# RELAYS.net
KiCad netlist of a schematic drawn in Altium Designer
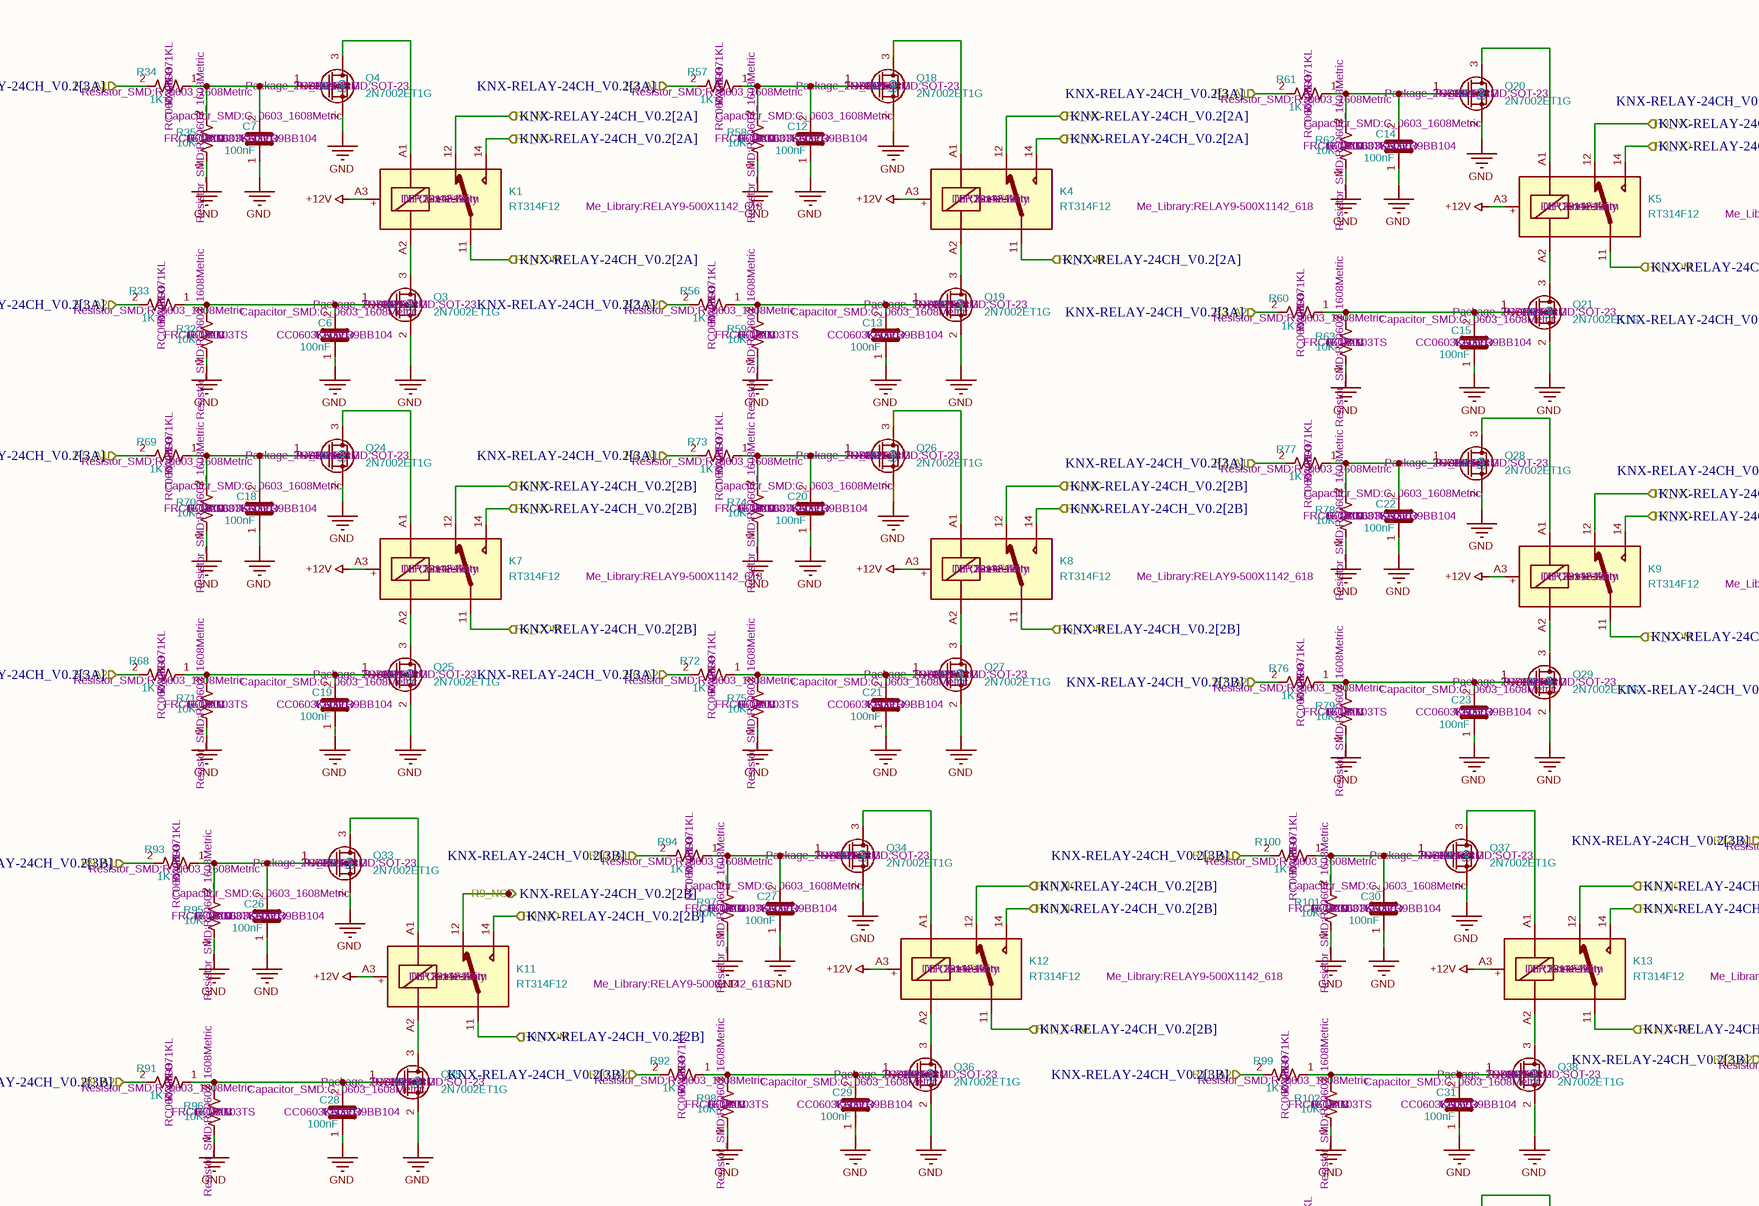
[diagram p0: RELAYS.SchDoc, top left]
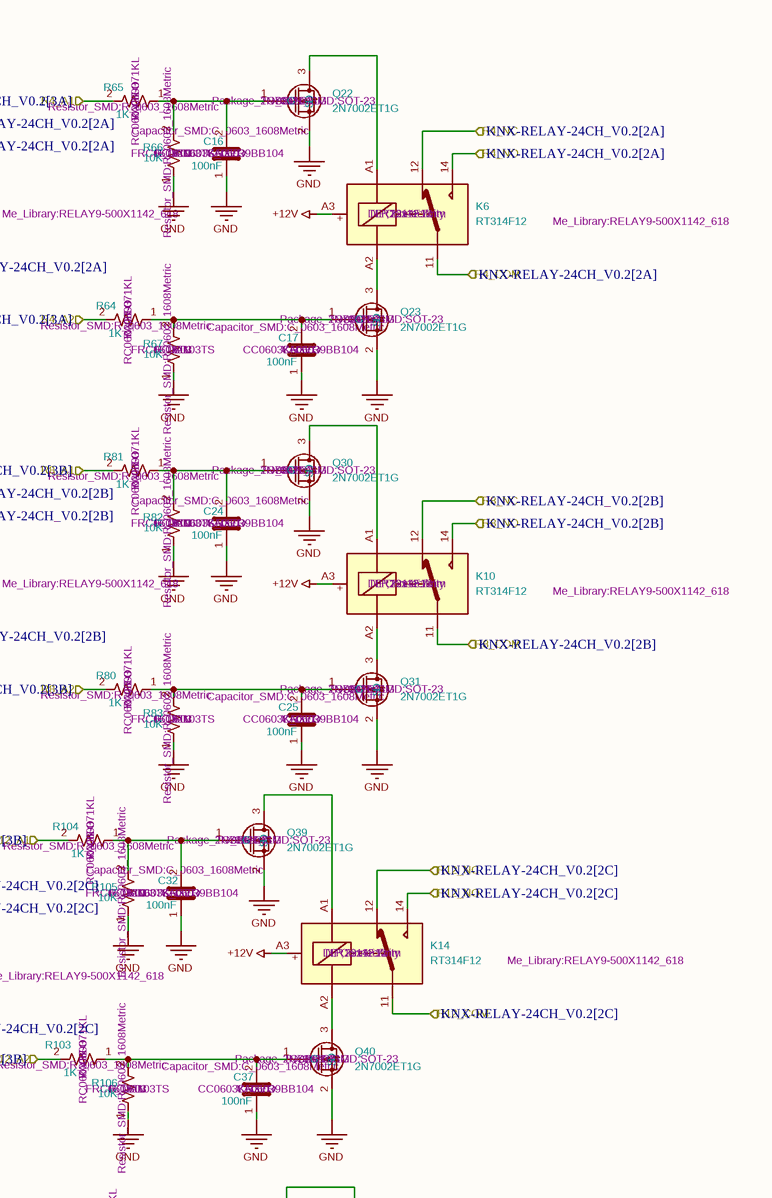
[diagram p1: RELAYS.SchDoc, top right]
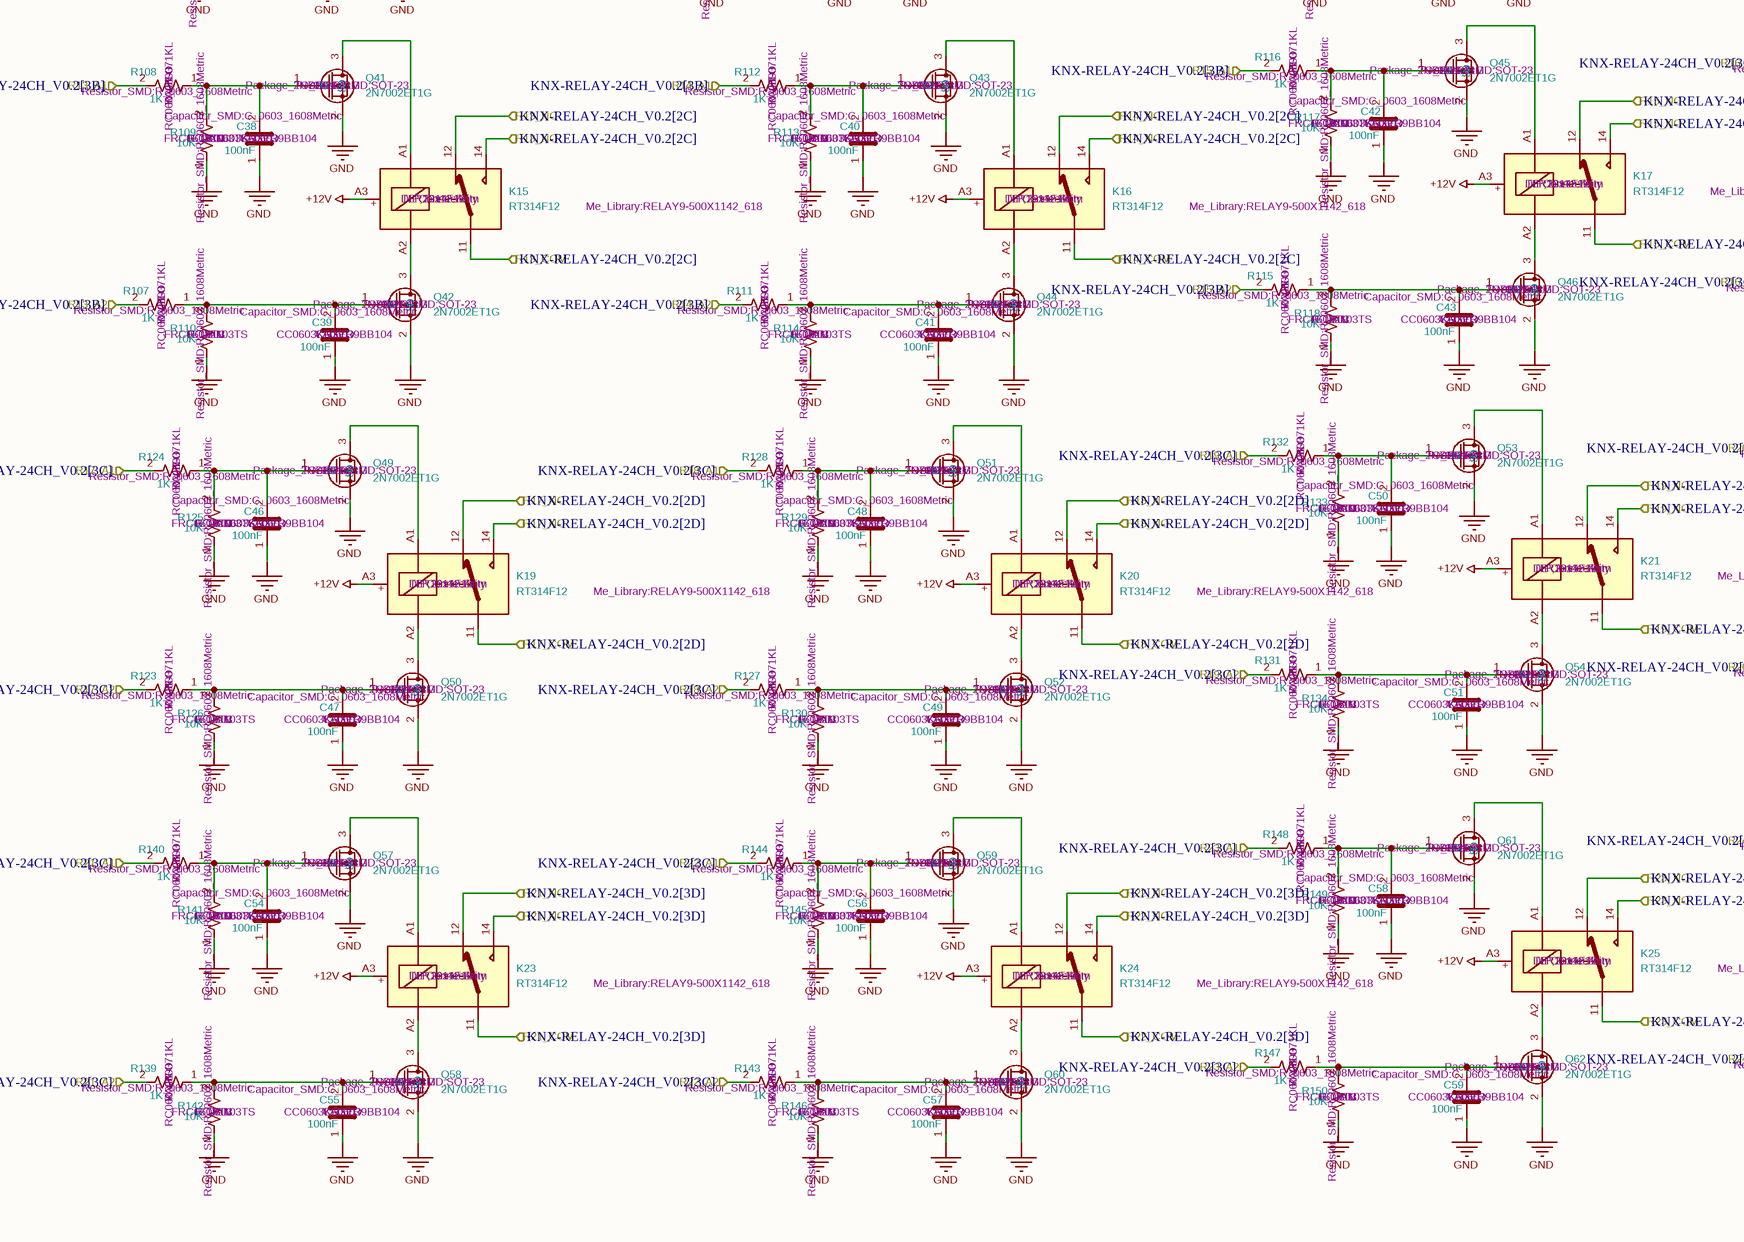
[diagram p2: RELAYS.SchDoc, bottom left]
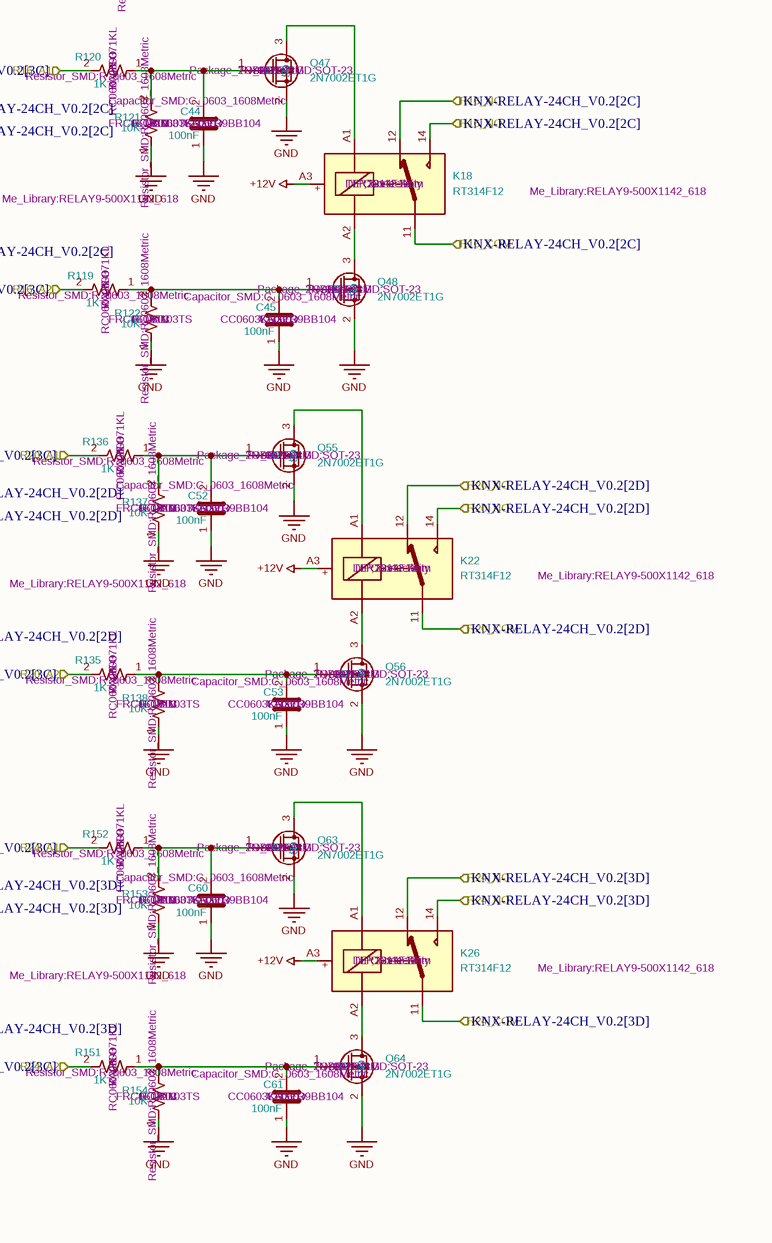
[diagram p3: RELAYS.SchDoc, bottom right]

(export (version "E")
  (design (tool "Eeschema 10.0.6"))
  (components
    (comp (ref "C6")
      (value "100nF")
      (footprint "Capacitor_SMD:C_0603_1608Metric")
      (fields
        (field (name "MANUFACTURER PART NUMBER") "CC0603KRX7R9BB104")
        (field (name "MANUFACTURER") "YAGEO")
        (field (name "PACKAGE") "C_0603")
      )
      (libsource (lib "*") (part "C_3"))
    )
    (comp (ref "C7")
      (value "100nF")
      (footprint "Capacitor_SMD:C_0603_1608Metric")
      (fields
        (field (name "MANUFACTURER PART NUMBER") "CC0603KRX7R9BB104")
        (field (name "MANUFACTURER") "YAGEO")
        (field (name "PACKAGE") "C_0603")
      )
      (libsource (lib "*") (part "C_3"))
    )
    (comp (ref "C12")
      (value "100nF")
      (footprint "Capacitor_SMD:C_0603_1608Metric")
      (fields
        (field (name "MANUFACTURER PART NUMBER") "CC0603KRX7R9BB104")
        (field (name "MANUFACTURER") "YAGEO")
        (field (name "PACKAGE") "C_0603")
      )
      (libsource (lib "*") (part "C_3"))
    )
    (comp (ref "C13")
      (value "100nF")
      (footprint "Capacitor_SMD:C_0603_1608Metric")
      (fields
        (field (name "MANUFACTURER PART NUMBER") "CC0603KRX7R9BB104")
        (field (name "MANUFACTURER") "YAGEO")
        (field (name "PACKAGE") "C_0603")
      )
      (libsource (lib "*") (part "C_3"))
    )
    (comp (ref "C14")
      (value "100nF")
      (footprint "Capacitor_SMD:C_0603_1608Metric")
      (fields
        (field (name "MANUFACTURER PART NUMBER") "CC0603KRX7R9BB104")
        (field (name "MANUFACTURER") "YAGEO")
        (field (name "PACKAGE") "C_0603")
      )
      (libsource (lib "*") (part "C_3"))
    )
    (comp (ref "C15")
      (value "100nF")
      (footprint "Capacitor_SMD:C_0603_1608Metric")
      (fields
        (field (name "MANUFACTURER PART NUMBER") "CC0603KRX7R9BB104")
        (field (name "MANUFACTURER") "YAGEO")
        (field (name "PACKAGE") "C_0603")
      )
      (libsource (lib "*") (part "C_3"))
    )
    (comp (ref "C16")
      (value "100nF")
      (footprint "Capacitor_SMD:C_0603_1608Metric")
      (fields
        (field (name "MANUFACTURER PART NUMBER") "CC0603KRX7R9BB104")
        (field (name "MANUFACTURER") "YAGEO")
        (field (name "PACKAGE") "C_0603")
      )
      (libsource (lib "*") (part "C_3"))
    )
    (comp (ref "C17")
      (value "100nF")
      (footprint "Capacitor_SMD:C_0603_1608Metric")
      (fields
        (field (name "MANUFACTURER PART NUMBER") "CC0603KRX7R9BB104")
        (field (name "MANUFACTURER") "YAGEO")
        (field (name "PACKAGE") "C_0603")
      )
      (libsource (lib "*") (part "C_3"))
    )
    (comp (ref "C18")
      (value "100nF")
      (footprint "Capacitor_SMD:C_0603_1608Metric")
      (fields
        (field (name "MANUFACTURER PART NUMBER") "CC0603KRX7R9BB104")
        (field (name "MANUFACTURER") "YAGEO")
        (field (name "PACKAGE") "C_0603")
      )
      (libsource (lib "*") (part "C_3"))
    )
    (comp (ref "C19")
      (value "100nF")
      (footprint "Capacitor_SMD:C_0603_1608Metric")
      (fields
        (field (name "MANUFACTURER PART NUMBER") "CC0603KRX7R9BB104")
        (field (name "MANUFACTURER") "YAGEO")
        (field (name "PACKAGE") "C_0603")
      )
      (libsource (lib "*") (part "C_3"))
    )
    (comp (ref "C20")
      (value "100nF")
      (footprint "Capacitor_SMD:C_0603_1608Metric")
      (fields
        (field (name "MANUFACTURER PART NUMBER") "CC0603KRX7R9BB104")
        (field (name "MANUFACTURER") "YAGEO")
        (field (name "PACKAGE") "C_0603")
      )
      (libsource (lib "*") (part "C_3"))
    )
    (comp (ref "C21")
      (value "100nF")
      (footprint "Capacitor_SMD:C_0603_1608Metric")
      (fields
        (field (name "MANUFACTURER PART NUMBER") "CC0603KRX7R9BB104")
        (field (name "MANUFACTURER") "YAGEO")
        (field (name "PACKAGE") "C_0603")
      )
      (libsource (lib "*") (part "C_3"))
    )
    (comp (ref "C22")
      (value "100nF")
      (footprint "Capacitor_SMD:C_0603_1608Metric")
      (fields
        (field (name "MANUFACTURER PART NUMBER") "CC0603KRX7R9BB104")
        (field (name "MANUFACTURER") "YAGEO")
        (field (name "PACKAGE") "C_0603")
      )
      (libsource (lib "*") (part "C_3"))
    )
    (comp (ref "C23")
      (value "100nF")
      (footprint "Capacitor_SMD:C_0603_1608Metric")
      (fields
        (field (name "MANUFACTURER PART NUMBER") "CC0603KRX7R9BB104")
        (field (name "MANUFACTURER") "YAGEO")
        (field (name "PACKAGE") "C_0603")
      )
      (libsource (lib "*") (part "C_3"))
    )
    (comp (ref "C24")
      (value "100nF")
      (footprint "Capacitor_SMD:C_0603_1608Metric")
      (fields
        (field (name "MANUFACTURER PART NUMBER") "CC0603KRX7R9BB104")
        (field (name "MANUFACTURER") "YAGEO")
        (field (name "PACKAGE") "C_0603")
      )
      (libsource (lib "*") (part "C_3"))
    )
    (comp (ref "C25")
      (value "100nF")
      (footprint "Capacitor_SMD:C_0603_1608Metric")
      (fields
        (field (name "MANUFACTURER PART NUMBER") "CC0603KRX7R9BB104")
        (field (name "MANUFACTURER") "YAGEO")
        (field (name "PACKAGE") "C_0603")
      )
      (libsource (lib "*") (part "C_3"))
    )
    (comp (ref "C26")
      (value "100nF")
      (footprint "Capacitor_SMD:C_0603_1608Metric")
      (fields
        (field (name "MANUFACTURER PART NUMBER") "CC0603KRX7R9BB104")
        (field (name "MANUFACTURER") "YAGEO")
        (field (name "PACKAGE") "C_0603")
      )
      (libsource (lib "*") (part "C_3"))
    )
    (comp (ref "C27")
      (value "100nF")
      (footprint "Capacitor_SMD:C_0603_1608Metric")
      (fields
        (field (name "MANUFACTURER PART NUMBER") "CC0603KRX7R9BB104")
        (field (name "MANUFACTURER") "YAGEO")
        (field (name "PACKAGE") "C_0603")
      )
      (libsource (lib "*") (part "C_3"))
    )
    (comp (ref "C28")
      (value "100nF")
      (footprint "Capacitor_SMD:C_0603_1608Metric")
      (fields
        (field (name "MANUFACTURER PART NUMBER") "CC0603KRX7R9BB104")
        (field (name "MANUFACTURER") "YAGEO")
        (field (name "PACKAGE") "C_0603")
      )
      (libsource (lib "*") (part "C_3"))
    )
    (comp (ref "C29")
      (value "100nF")
      (footprint "Capacitor_SMD:C_0603_1608Metric")
      (fields
        (field (name "MANUFACTURER PART NUMBER") "CC0603KRX7R9BB104")
        (field (name "MANUFACTURER") "YAGEO")
        (field (name "PACKAGE") "C_0603")
      )
      (libsource (lib "*") (part "C_3"))
    )
    (comp (ref "C30")
      (value "100nF")
      (footprint "Capacitor_SMD:C_0603_1608Metric")
      (fields
        (field (name "MANUFACTURER PART NUMBER") "CC0603KRX7R9BB104")
        (field (name "MANUFACTURER") "YAGEO")
        (field (name "PACKAGE") "C_0603")
      )
      (libsource (lib "*") (part "C_3"))
    )
    (comp (ref "C31")
      (value "100nF")
      (footprint "Capacitor_SMD:C_0603_1608Metric")
      (fields
        (field (name "MANUFACTURER PART NUMBER") "CC0603KRX7R9BB104")
        (field (name "MANUFACTURER") "YAGEO")
        (field (name "PACKAGE") "C_0603")
      )
      (libsource (lib "*") (part "C_3"))
    )
    (comp (ref "C32")
      (value "100nF")
      (footprint "Capacitor_SMD:C_0603_1608Metric")
      (fields
        (field (name "MANUFACTURER PART NUMBER") "CC0603KRX7R9BB104")
        (field (name "MANUFACTURER") "YAGEO")
        (field (name "PACKAGE") "C_0603")
      )
      (libsource (lib "*") (part "C_3"))
    )
    (comp (ref "C37")
      (value "100nF")
      (footprint "Capacitor_SMD:C_0603_1608Metric")
      (fields
        (field (name "MANUFACTURER PART NUMBER") "CC0603KRX7R9BB104")
        (field (name "MANUFACTURER") "YAGEO")
        (field (name "PACKAGE") "C_0603")
      )
      (libsource (lib "*") (part "C_3"))
    )
    (comp (ref "C38")
      (value "100nF")
      (footprint "Capacitor_SMD:C_0603_1608Metric")
      (fields
        (field (name "MANUFACTURER PART NUMBER") "CC0603KRX7R9BB104")
        (field (name "MANUFACTURER") "YAGEO")
        (field (name "PACKAGE") "C_0603")
      )
      (libsource (lib "*") (part "C_3"))
    )
    (comp (ref "C39")
      (value "100nF")
      (footprint "Capacitor_SMD:C_0603_1608Metric")
      (fields
        (field (name "MANUFACTURER PART NUMBER") "CC0603KRX7R9BB104")
        (field (name "MANUFACTURER") "YAGEO")
        (field (name "PACKAGE") "C_0603")
      )
      (libsource (lib "*") (part "C_3"))
    )
    (comp (ref "C40")
      (value "100nF")
      (footprint "Capacitor_SMD:C_0603_1608Metric")
      (fields
        (field (name "MANUFACTURER PART NUMBER") "CC0603KRX7R9BB104")
        (field (name "MANUFACTURER") "YAGEO")
        (field (name "PACKAGE") "C_0603")
      )
      (libsource (lib "*") (part "C_3"))
    )
    (comp (ref "C41")
      (value "100nF")
      (footprint "Capacitor_SMD:C_0603_1608Metric")
      (fields
        (field (name "MANUFACTURER PART NUMBER") "CC0603KRX7R9BB104")
        (field (name "MANUFACTURER") "YAGEO")
        (field (name "PACKAGE") "C_0603")
      )
      (libsource (lib "*") (part "C_3"))
    )
    (comp (ref "C42")
      (value "100nF")
      (footprint "Capacitor_SMD:C_0603_1608Metric")
      (fields
        (field (name "MANUFACTURER PART NUMBER") "CC0603KRX7R9BB104")
        (field (name "MANUFACTURER") "YAGEO")
        (field (name "PACKAGE") "C_0603")
      )
      (libsource (lib "*") (part "C_3"))
    )
    (comp (ref "C43")
      (value "100nF")
      (footprint "Capacitor_SMD:C_0603_1608Metric")
      (fields
        (field (name "MANUFACTURER PART NUMBER") "CC0603KRX7R9BB104")
        (field (name "MANUFACTURER") "YAGEO")
        (field (name "PACKAGE") "C_0603")
      )
      (libsource (lib "*") (part "C_3"))
    )
    (comp (ref "C44")
      (value "100nF")
      (footprint "Capacitor_SMD:C_0603_1608Metric")
      (fields
        (field (name "MANUFACTURER PART NUMBER") "CC0603KRX7R9BB104")
        (field (name "MANUFACTURER") "YAGEO")
        (field (name "PACKAGE") "C_0603")
      )
      (libsource (lib "*") (part "C_3"))
    )
    (comp (ref "C45")
      (value "100nF")
      (footprint "Capacitor_SMD:C_0603_1608Metric")
      (fields
        (field (name "MANUFACTURER PART NUMBER") "CC0603KRX7R9BB104")
        (field (name "MANUFACTURER") "YAGEO")
        (field (name "PACKAGE") "C_0603")
      )
      (libsource (lib "*") (part "C_3"))
    )
    (comp (ref "C46")
      (value "100nF")
      (footprint "Capacitor_SMD:C_0603_1608Metric")
      (fields
        (field (name "MANUFACTURER PART NUMBER") "CC0603KRX7R9BB104")
        (field (name "MANUFACTURER") "YAGEO")
        (field (name "PACKAGE") "C_0603")
      )
      (libsource (lib "*") (part "C_3"))
    )
    (comp (ref "C47")
      (value "100nF")
      (footprint "Capacitor_SMD:C_0603_1608Metric")
      (fields
        (field (name "MANUFACTURER PART NUMBER") "CC0603KRX7R9BB104")
        (field (name "MANUFACTURER") "YAGEO")
        (field (name "PACKAGE") "C_0603")
      )
      (libsource (lib "*") (part "C_3"))
    )
    (comp (ref "C48")
      (value "100nF")
      (footprint "Capacitor_SMD:C_0603_1608Metric")
      (fields
        (field (name "MANUFACTURER PART NUMBER") "CC0603KRX7R9BB104")
        (field (name "MANUFACTURER") "YAGEO")
        (field (name "PACKAGE") "C_0603")
      )
      (libsource (lib "*") (part "C_3"))
    )
    (comp (ref "C49")
      (value "100nF")
      (footprint "Capacitor_SMD:C_0603_1608Metric")
      (fields
        (field (name "MANUFACTURER PART NUMBER") "CC0603KRX7R9BB104")
        (field (name "MANUFACTURER") "YAGEO")
        (field (name "PACKAGE") "C_0603")
      )
      (libsource (lib "*") (part "C_3"))
    )
    (comp (ref "C50")
      (value "100nF")
      (footprint "Capacitor_SMD:C_0603_1608Metric")
      (fields
        (field (name "MANUFACTURER PART NUMBER") "CC0603KRX7R9BB104")
        (field (name "MANUFACTURER") "YAGEO")
        (field (name "PACKAGE") "C_0603")
      )
      (libsource (lib "*") (part "C_3"))
    )
    (comp (ref "C51")
      (value "100nF")
      (footprint "Capacitor_SMD:C_0603_1608Metric")
      (fields
        (field (name "MANUFACTURER PART NUMBER") "CC0603KRX7R9BB104")
        (field (name "MANUFACTURER") "YAGEO")
        (field (name "PACKAGE") "C_0603")
      )
      (libsource (lib "*") (part "C_3"))
    )
    (comp (ref "C52")
      (value "100nF")
      (footprint "Capacitor_SMD:C_0603_1608Metric")
      (fields
        (field (name "MANUFACTURER PART NUMBER") "CC0603KRX7R9BB104")
        (field (name "MANUFACTURER") "YAGEO")
        (field (name "PACKAGE") "C_0603")
      )
      (libsource (lib "*") (part "C_3"))
    )
    (comp (ref "C53")
      (value "100nF")
      (footprint "Capacitor_SMD:C_0603_1608Metric")
      (fields
        (field (name "MANUFACTURER PART NUMBER") "CC0603KRX7R9BB104")
        (field (name "MANUFACTURER") "YAGEO")
        (field (name "PACKAGE") "C_0603")
      )
      (libsource (lib "*") (part "C_3"))
    )
    (comp (ref "C54")
      (value "100nF")
      (footprint "Capacitor_SMD:C_0603_1608Metric")
      (fields
        (field (name "MANUFACTURER PART NUMBER") "CC0603KRX7R9BB104")
        (field (name "MANUFACTURER") "YAGEO")
        (field (name "PACKAGE") "C_0603")
      )
      (libsource (lib "*") (part "C_3"))
    )
    (comp (ref "C55")
      (value "100nF")
      (footprint "Capacitor_SMD:C_0603_1608Metric")
      (fields
        (field (name "MANUFACTURER PART NUMBER") "CC0603KRX7R9BB104")
        (field (name "MANUFACTURER") "YAGEO")
        (field (name "PACKAGE") "C_0603")
      )
      (libsource (lib "*") (part "C_3"))
    )
    (comp (ref "C56")
      (value "100nF")
      (footprint "Capacitor_SMD:C_0603_1608Metric")
      (fields
        (field (name "MANUFACTURER PART NUMBER") "CC0603KRX7R9BB104")
        (field (name "MANUFACTURER") "YAGEO")
        (field (name "PACKAGE") "C_0603")
      )
      (libsource (lib "*") (part "C_3"))
    )
    (comp (ref "C57")
      (value "100nF")
      (footprint "Capacitor_SMD:C_0603_1608Metric")
      (fields
        (field (name "MANUFACTURER PART NUMBER") "CC0603KRX7R9BB104")
        (field (name "MANUFACTURER") "YAGEO")
        (field (name "PACKAGE") "C_0603")
      )
      (libsource (lib "*") (part "C_3"))
    )
    (comp (ref "C58")
      (value "100nF")
      (footprint "Capacitor_SMD:C_0603_1608Metric")
      (fields
        (field (name "MANUFACTURER PART NUMBER") "CC0603KRX7R9BB104")
        (field (name "MANUFACTURER") "YAGEO")
        (field (name "PACKAGE") "C_0603")
      )
      (libsource (lib "*") (part "C_3"))
    )
    (comp (ref "C59")
      (value "100nF")
      (footprint "Capacitor_SMD:C_0603_1608Metric")
      (fields
        (field (name "MANUFACTURER PART NUMBER") "CC0603KRX7R9BB104")
        (field (name "MANUFACTURER") "YAGEO")
        (field (name "PACKAGE") "C_0603")
      )
      (libsource (lib "*") (part "C_3"))
    )
    (comp (ref "C60")
      (value "100nF")
      (footprint "Capacitor_SMD:C_0603_1608Metric")
      (fields
        (field (name "MANUFACTURER PART NUMBER") "CC0603KRX7R9BB104")
        (field (name "MANUFACTURER") "YAGEO")
        (field (name "PACKAGE") "C_0603")
      )
      (libsource (lib "*") (part "C_3"))
    )
    (comp (ref "C61")
      (value "100nF")
      (footprint "Capacitor_SMD:C_0603_1608Metric")
      (fields
        (field (name "MANUFACTURER PART NUMBER") "CC0603KRX7R9BB104")
        (field (name "MANUFACTURER") "YAGEO")
        (field (name "PACKAGE") "C_0603")
      )
      (libsource (lib "*") (part "C_3"))
    )
    (comp (ref "K1")
      (value "RT314F12")
      (footprint "Me_Library:RELAY9-500X1142_618")
      (fields
        (field (name "MANUFACTURER PART NUMBER") "RT314F12")
        (field (name "MANUFACTURER") "TE Connectivity")
        (field (name "PACKAGE") "DIP,29x12.7mm")
      )
      (libsource (lib "Me_Library") (part "RT314A03"))
    )
    (comp (ref "K4")
      (value "RT314F12")
      (footprint "Me_Library:RELAY9-500X1142_618")
      (fields
        (field (name "MANUFACTURER PART NUMBER") "RT314F12")
        (field (name "MANUFACTURER") "TE Connectivity")
        (field (name "PACKAGE") "DIP,29x12.7mm")
      )
      (libsource (lib "Me_Library") (part "RT314A03"))
    )
    (comp (ref "K5")
      (value "RT314F12")
      (footprint "Me_Library:RELAY9-500X1142_618")
      (fields
        (field (name "MANUFACTURER PART NUMBER") "RT314F12")
        (field (name "MANUFACTURER") "TE Connectivity")
        (field (name "PACKAGE") "DIP,29x12.7mm")
      )
      (libsource (lib "Me_Library") (part "RT314A03"))
    )
    (comp (ref "K6")
      (value "RT314F12")
      (footprint "Me_Library:RELAY9-500X1142_618")
      (fields
        (field (name "MANUFACTURER PART NUMBER") "RT314F12")
        (field (name "MANUFACTURER") "TE Connectivity")
        (field (name "PACKAGE") "DIP,29x12.7mm")
      )
      (libsource (lib "Me_Library") (part "RT314A03"))
    )
    (comp (ref "K7")
      (value "RT314F12")
      (footprint "Me_Library:RELAY9-500X1142_618")
      (fields
        (field (name "MANUFACTURER PART NUMBER") "RT314F12")
        (field (name "MANUFACTURER") "TE Connectivity")
        (field (name "PACKAGE") "DIP,29x12.7mm")
      )
      (libsource (lib "Me_Library") (part "RT314A03"))
    )
    (comp (ref "K8")
      (value "RT314F12")
      (footprint "Me_Library:RELAY9-500X1142_618")
      (fields
        (field (name "MANUFACTURER PART NUMBER") "RT314F12")
        (field (name "MANUFACTURER") "TE Connectivity")
        (field (name "PACKAGE") "DIP,29x12.7mm")
      )
      (libsource (lib "Me_Library") (part "RT314A03"))
    )
    (comp (ref "K9")
      (value "RT314F12")
      (footprint "Me_Library:RELAY9-500X1142_618")
      (fields
        (field (name "MANUFACTURER PART NUMBER") "RT314F12")
        (field (name "MANUFACTURER") "TE Connectivity")
        (field (name "PACKAGE") "DIP,29x12.7mm")
      )
      (libsource (lib "Me_Library") (part "RT314A03"))
    )
    (comp (ref "K10")
      (value "RT314F12")
      (footprint "Me_Library:RELAY9-500X1142_618")
      (fields
        (field (name "MANUFACTURER PART NUMBER") "RT314F12")
        (field (name "MANUFACTURER") "TE Connectivity")
        (field (name "PACKAGE") "DIP,29x12.7mm")
      )
      (libsource (lib "Me_Library") (part "RT314A03"))
    )
    (comp (ref "K11")
      (value "RT314F12")
      (footprint "Me_Library:RELAY9-500X1142_618")
      (fields
        (field (name "MANUFACTURER PART NUMBER") "RT314F12")
        (field (name "MANUFACTURER") "TE Connectivity")
        (field (name "PACKAGE") "DIP,29x12.7mm")
      )
      (libsource (lib "Me_Library") (part "RT314A03"))
    )
    (comp (ref "K12")
      (value "RT314F12")
      (footprint "Me_Library:RELAY9-500X1142_618")
      (fields
        (field (name "MANUFACTURER PART NUMBER") "RT314F12")
        (field (name "MANUFACTURER") "TE Connectivity")
        (field (name "PACKAGE") "DIP,29x12.7mm")
      )
      (libsource (lib "Me_Library") (part "RT314A03"))
    )
    (comp (ref "K13")
      (value "RT314F12")
      (footprint "Me_Library:RELAY9-500X1142_618")
      (fields
        (field (name "MANUFACTURER PART NUMBER") "RT314F12")
        (field (name "MANUFACTURER") "TE Connectivity")
        (field (name "PACKAGE") "DIP,29x12.7mm")
      )
      (libsource (lib "Me_Library") (part "RT314A03"))
    )
    (comp (ref "K14")
      (value "RT314F12")
      (footprint "Me_Library:RELAY9-500X1142_618")
      (fields
        (field (name "MANUFACTURER PART NUMBER") "RT314F12")
        (field (name "MANUFACTURER") "TE Connectivity")
        (field (name "PACKAGE") "DIP,29x12.7mm")
      )
      (libsource (lib "Me_Library") (part "RT314A03"))
    )
    (comp (ref "K15")
      (value "RT314F12")
      (footprint "Me_Library:RELAY9-500X1142_618")
      (fields
        (field (name "MANUFACTURER PART NUMBER") "RT314F12")
        (field (name "MANUFACTURER") "TE Connectivity")
        (field (name "PACKAGE") "DIP,29x12.7mm")
      )
      (libsource (lib "Me_Library") (part "RT314A03"))
    )
    (comp (ref "K16")
      (value "RT314F12")
      (footprint "Me_Library:RELAY9-500X1142_618")
      (fields
        (field (name "MANUFACTURER PART NUMBER") "RT314F12")
        (field (name "MANUFACTURER") "TE Connectivity")
        (field (name "PACKAGE") "DIP,29x12.7mm")
      )
      (libsource (lib "Me_Library") (part "RT314A03"))
    )
    (comp (ref "K17")
      (value "RT314F12")
      (footprint "Me_Library:RELAY9-500X1142_618")
      (fields
        (field (name "MANUFACTURER PART NUMBER") "RT314F12")
        (field (name "MANUFACTURER") "TE Connectivity")
        (field (name "PACKAGE") "DIP,29x12.7mm")
      )
      (libsource (lib "Me_Library") (part "RT314A03"))
    )
    (comp (ref "K18")
      (value "RT314F12")
      (footprint "Me_Library:RELAY9-500X1142_618")
      (fields
        (field (name "MANUFACTURER PART NUMBER") "RT314F12")
        (field (name "MANUFACTURER") "TE Connectivity")
        (field (name "PACKAGE") "DIP,29x12.7mm")
      )
      (libsource (lib "Me_Library") (part "RT314A03"))
    )
    (comp (ref "K19")
      (value "RT314F12")
      (footprint "Me_Library:RELAY9-500X1142_618")
      (fields
        (field (name "MANUFACTURER PART NUMBER") "RT314F12")
        (field (name "MANUFACTURER") "TE Connectivity")
        (field (name "PACKAGE") "DIP,29x12.7mm")
      )
      (libsource (lib "Me_Library") (part "RT314A03"))
    )
    (comp (ref "K20")
      (value "RT314F12")
      (footprint "Me_Library:RELAY9-500X1142_618")
      (fields
        (field (name "MANUFACTURER PART NUMBER") "RT314F12")
        (field (name "MANUFACTURER") "TE Connectivity")
        (field (name "PACKAGE") "DIP,29x12.7mm")
      )
      (libsource (lib "Me_Library") (part "RT314A03"))
    )
    (comp (ref "K21")
      (value "RT314F12")
      (footprint "Me_Library:RELAY9-500X1142_618")
      (fields
        (field (name "MANUFACTURER PART NUMBER") "RT314F12")
        (field (name "MANUFACTURER") "TE Connectivity")
        (field (name "PACKAGE") "DIP,29x12.7mm")
      )
      (libsource (lib "Me_Library") (part "RT314A03"))
    )
    (comp (ref "K22")
      (value "RT314F12")
      (footprint "Me_Library:RELAY9-500X1142_618")
      (fields
        (field (name "MANUFACTURER PART NUMBER") "RT314F12")
        (field (name "MANUFACTURER") "TE Connectivity")
        (field (name "PACKAGE") "DIP,29x12.7mm")
      )
      (libsource (lib "Me_Library") (part "RT314A03"))
    )
    (comp (ref "K23")
      (value "RT314F12")
      (footprint "Me_Library:RELAY9-500X1142_618")
      (fields
        (field (name "MANUFACTURER PART NUMBER") "RT314F12")
        (field (name "MANUFACTURER") "TE Connectivity")
        (field (name "PACKAGE") "DIP,29x12.7mm")
      )
      (libsource (lib "Me_Library") (part "RT314A03"))
    )
    (comp (ref "K24")
      (value "RT314F12")
      (footprint "Me_Library:RELAY9-500X1142_618")
      (fields
        (field (name "MANUFACTURER PART NUMBER") "RT314F12")
        (field (name "MANUFACTURER") "TE Connectivity")
        (field (name "PACKAGE") "DIP,29x12.7mm")
      )
      (libsource (lib "Me_Library") (part "RT314A03"))
    )
    (comp (ref "K25")
      (value "RT314F12")
      (footprint "Me_Library:RELAY9-500X1142_618")
      (fields
        (field (name "MANUFACTURER PART NUMBER") "RT314F12")
        (field (name "MANUFACTURER") "TE Connectivity")
        (field (name "PACKAGE") "DIP,29x12.7mm")
      )
      (libsource (lib "Me_Library") (part "RT314A03"))
    )
    (comp (ref "K26")
      (value "RT314F12")
      (footprint "Me_Library:RELAY9-500X1142_618")
      (fields
        (field (name "MANUFACTURER PART NUMBER") "RT314F12")
        (field (name "MANUFACTURER") "TE Connectivity")
        (field (name "PACKAGE") "DIP,29x12.7mm")
      )
      (libsource (lib "Me_Library") (part "RT314A03"))
    )
    (comp (ref "Q3")
      (value "2N7002ET1G")
      (footprint "Package_TO_SOT_SMD:SOT-23")
      (fields
        (field (name "MANUFACTURER PART NUMBER") "2N7002ET1G")
        (field (name "MANUFACTURER") "onsemi")
        (field (name "PACKAGE") "SOT-23")
      )
      (libsource (lib "Transistor_FET_Other") (part "Q_NMOS_Depletion_GSD"))
    )
    (comp (ref "Q4")
      (value "2N7002ET1G")
      (footprint "Package_TO_SOT_SMD:SOT-23")
      (fields
        (field (name "MANUFACTURER PART NUMBER") "2N7002ET1G")
        (field (name "MANUFACTURER") "onsemi")
        (field (name "PACKAGE") "SOT-23")
      )
      (libsource (lib "Transistor_FET_Other") (part "Q_NMOS_Depletion_GSD"))
    )
    (comp (ref "Q18")
      (value "2N7002ET1G")
      (footprint "Package_TO_SOT_SMD:SOT-23")
      (fields
        (field (name "MANUFACTURER PART NUMBER") "2N7002ET1G")
        (field (name "MANUFACTURER") "onsemi")
        (field (name "PACKAGE") "SOT-23")
      )
      (libsource (lib "Transistor_FET_Other") (part "Q_NMOS_Depletion_GSD"))
    )
    (comp (ref "Q19")
      (value "2N7002ET1G")
      (footprint "Package_TO_SOT_SMD:SOT-23")
      (fields
        (field (name "MANUFACTURER PART NUMBER") "2N7002ET1G")
        (field (name "MANUFACTURER") "onsemi")
        (field (name "PACKAGE") "SOT-23")
      )
      (libsource (lib "Transistor_FET_Other") (part "Q_NMOS_Depletion_GSD"))
    )
    (comp (ref "Q20")
      (value "2N7002ET1G")
      (footprint "Package_TO_SOT_SMD:SOT-23")
      (fields
        (field (name "MANUFACTURER PART NUMBER") "2N7002ET1G")
        (field (name "MANUFACTURER") "onsemi")
        (field (name "PACKAGE") "SOT-23")
      )
      (libsource (lib "Transistor_FET_Other") (part "Q_NMOS_Depletion_GSD"))
    )
    (comp (ref "Q21")
      (value "2N7002ET1G")
      (footprint "Package_TO_SOT_SMD:SOT-23")
      (fields
        (field (name "MANUFACTURER PART NUMBER") "2N7002ET1G")
        (field (name "MANUFACTURER") "onsemi")
        (field (name "PACKAGE") "SOT-23")
      )
      (libsource (lib "Transistor_FET_Other") (part "Q_NMOS_Depletion_GSD"))
    )
    (comp (ref "Q22")
      (value "2N7002ET1G")
      (footprint "Package_TO_SOT_SMD:SOT-23")
      (fields
        (field (name "MANUFACTURER PART NUMBER") "2N7002ET1G")
        (field (name "MANUFACTURER") "onsemi")
        (field (name "PACKAGE") "SOT-23")
      )
      (libsource (lib "Transistor_FET_Other") (part "Q_NMOS_Depletion_GSD"))
    )
    (comp (ref "Q23")
      (value "2N7002ET1G")
      (footprint "Package_TO_SOT_SMD:SOT-23")
      (fields
        (field (name "MANUFACTURER PART NUMBER") "2N7002ET1G")
        (field (name "MANUFACTURER") "onsemi")
        (field (name "PACKAGE") "SOT-23")
      )
      (libsource (lib "Transistor_FET_Other") (part "Q_NMOS_Depletion_GSD"))
    )
    (comp (ref "Q24")
      (value "2N7002ET1G")
      (footprint "Package_TO_SOT_SMD:SOT-23")
      (fields
        (field (name "MANUFACTURER PART NUMBER") "2N7002ET1G")
        (field (name "MANUFACTURER") "onsemi")
        (field (name "PACKAGE") "SOT-23")
      )
      (libsource (lib "Transistor_FET_Other") (part "Q_NMOS_Depletion_GSD"))
    )
    (comp (ref "Q25")
      (value "2N7002ET1G")
      (footprint "Package_TO_SOT_SMD:SOT-23")
      (fields
        (field (name "MANUFACTURER PART NUMBER") "2N7002ET1G")
        (field (name "MANUFACTURER") "onsemi")
        (field (name "PACKAGE") "SOT-23")
      )
      (libsource (lib "Transistor_FET_Other") (part "Q_NMOS_Depletion_GSD"))
    )
    (comp (ref "Q26")
      (value "2N7002ET1G")
      (footprint "Package_TO_SOT_SMD:SOT-23")
      (fields
        (field (name "MANUFACTURER PART NUMBER") "2N7002ET1G")
        (field (name "MANUFACTURER") "onsemi")
        (field (name "PACKAGE") "SOT-23")
      )
      (libsource (lib "Transistor_FET_Other") (part "Q_NMOS_Depletion_GSD"))
    )
    (comp (ref "Q27")
      (value "2N7002ET1G")
      (footprint "Package_TO_SOT_SMD:SOT-23")
      (fields
        (field (name "MANUFACTURER PART NUMBER") "2N7002ET1G")
        (field (name "MANUFACTURER") "onsemi")
        (field (name "PACKAGE") "SOT-23")
      )
      (libsource (lib "Transistor_FET_Other") (part "Q_NMOS_Depletion_GSD"))
    )
    (comp (ref "Q28")
      (value "2N7002ET1G")
      (footprint "Package_TO_SOT_SMD:SOT-23")
      (fields
        (field (name "MANUFACTURER PART NUMBER") "2N7002ET1G")
        (field (name "MANUFACTURER") "onsemi")
        (field (name "PACKAGE") "SOT-23")
      )
      (libsource (lib "Transistor_FET_Other") (part "Q_NMOS_Depletion_GSD"))
    )
    (comp (ref "Q29")
      (value "2N7002ET1G")
      (footprint "Package_TO_SOT_SMD:SOT-23")
      (fields
        (field (name "MANUFACTURER PART NUMBER") "2N7002ET1G")
        (field (name "MANUFACTURER") "onsemi")
        (field (name "PACKAGE") "SOT-23")
      )
      (libsource (lib "Transistor_FET_Other") (part "Q_NMOS_Depletion_GSD"))
    )
    (comp (ref "Q30")
      (value "2N7002ET1G")
      (footprint "Package_TO_SOT_SMD:SOT-23")
      (fields
        (field (name "MANUFACTURER PART NUMBER") "2N7002ET1G")
        (field (name "MANUFACTURER") "onsemi")
        (field (name "PACKAGE") "SOT-23")
      )
      (libsource (lib "Transistor_FET_Other") (part "Q_NMOS_Depletion_GSD"))
    )
    (comp (ref "Q31")
      (value "2N7002ET1G")
      (footprint "Package_TO_SOT_SMD:SOT-23")
      (fields
        (field (name "MANUFACTURER PART NUMBER") "2N7002ET1G")
        (field (name "MANUFACTURER") "onsemi")
        (field (name "PACKAGE") "SOT-23")
      )
      (libsource (lib "Transistor_FET_Other") (part "Q_NMOS_Depletion_GSD"))
    )
    (comp (ref "Q33")
      (value "2N7002ET1G")
      (footprint "Package_TO_SOT_SMD:SOT-23")
      (fields
        (field (name "MANUFACTURER PART NUMBER") "2N7002ET1G")
        (field (name "MANUFACTURER") "onsemi")
        (field (name "PACKAGE") "SOT-23")
      )
      (libsource (lib "Transistor_FET_Other") (part "Q_NMOS_Depletion_GSD"))
    )
    (comp (ref "Q34")
      (value "2N7002ET1G")
      (footprint "Package_TO_SOT_SMD:SOT-23")
      (fields
        (field (name "MANUFACTURER PART NUMBER") "2N7002ET1G")
        (field (name "MANUFACTURER") "onsemi")
        (field (name "PACKAGE") "SOT-23")
      )
      (libsource (lib "Transistor_FET_Other") (part "Q_NMOS_Depletion_GSD"))
    )
    (comp (ref "Q35")
      (value "2N7002ET1G")
      (footprint "Package_TO_SOT_SMD:SOT-23")
      (fields
        (field (name "MANUFACTURER PART NUMBER") "2N7002ET1G")
        (field (name "MANUFACTURER") "onsemi")
        (field (name "PACKAGE") "SOT-23")
      )
      (libsource (lib "Transistor_FET_Other") (part "Q_NMOS_Depletion_GSD"))
    )
    (comp (ref "Q36")
      (value "2N7002ET1G")
      (footprint "Package_TO_SOT_SMD:SOT-23")
      (fields
        (field (name "MANUFACTURER PART NUMBER") "2N7002ET1G")
        (field (name "MANUFACTURER") "onsemi")
        (field (name "PACKAGE") "SOT-23")
      )
      (libsource (lib "Transistor_FET_Other") (part "Q_NMOS_Depletion_GSD"))
    )
    (comp (ref "Q37")
      (value "2N7002ET1G")
      (footprint "Package_TO_SOT_SMD:SOT-23")
      (fields
        (field (name "MANUFACTURER PART NUMBER") "2N7002ET1G")
        (field (name "MANUFACTURER") "onsemi")
        (field (name "PACKAGE") "SOT-23")
      )
      (libsource (lib "Transistor_FET_Other") (part "Q_NMOS_Depletion_GSD"))
    )
    (comp (ref "Q38")
      (value "2N7002ET1G")
      (footprint "Package_TO_SOT_SMD:SOT-23")
      (fields
        (field (name "MANUFACTURER PART NUMBER") "2N7002ET1G")
        (field (name "MANUFACTURER") "onsemi")
        (field (name "PACKAGE") "SOT-23")
      )
      (libsource (lib "Transistor_FET_Other") (part "Q_NMOS_Depletion_GSD"))
    )
    (comp (ref "Q39")
      (value "2N7002ET1G")
      (footprint "Package_TO_SOT_SMD:SOT-23")
      (fields
        (field (name "MANUFACTURER PART NUMBER") "2N7002ET1G")
        (field (name "MANUFACTURER") "onsemi")
        (field (name "PACKAGE") "SOT-23")
      )
      (libsource (lib "Transistor_FET_Other") (part "Q_NMOS_Depletion_GSD"))
    )
    (comp (ref "Q40")
      (value "2N7002ET1G")
      (footprint "Package_TO_SOT_SMD:SOT-23")
      (fields
        (field (name "MANUFACTURER PART NUMBER") "2N7002ET1G")
        (field (name "MANUFACTURER") "onsemi")
        (field (name "PACKAGE") "SOT-23")
      )
      (libsource (lib "Transistor_FET_Other") (part "Q_NMOS_Depletion_GSD"))
    )
    (comp (ref "Q41")
      (value "2N7002ET1G")
      (footprint "Package_TO_SOT_SMD:SOT-23")
      (fields
        (field (name "MANUFACTURER PART NUMBER") "2N7002ET1G")
        (field (name "MANUFACTURER") "onsemi")
        (field (name "PACKAGE") "SOT-23")
      )
      (libsource (lib "Transistor_FET_Other") (part "Q_NMOS_Depletion_GSD"))
    )
    (comp (ref "Q42")
      (value "2N7002ET1G")
      (footprint "Package_TO_SOT_SMD:SOT-23")
      (fields
        (field (name "MANUFACTURER PART NUMBER") "2N7002ET1G")
        (field (name "MANUFACTURER") "onsemi")
        (field (name "PACKAGE") "SOT-23")
      )
      (libsource (lib "Transistor_FET_Other") (part "Q_NMOS_Depletion_GSD"))
    )
    (comp (ref "Q43")
      (value "2N7002ET1G")
      (footprint "Package_TO_SOT_SMD:SOT-23")
      (fields
        (field (name "MANUFACTURER PART NUMBER") "2N7002ET1G")
        (field (name "MANUFACTURER") "onsemi")
        (field (name "PACKAGE") "SOT-23")
      )
      (libsource (lib "Transistor_FET_Other") (part "Q_NMOS_Depletion_GSD"))
    )
    (comp (ref "Q44")
      (value "2N7002ET1G")
      (footprint "Package_TO_SOT_SMD:SOT-23")
      (fields
        (field (name "MANUFACTURER PART NUMBER") "2N7002ET1G")
        (field (name "MANUFACTURER") "onsemi")
        (field (name "PACKAGE") "SOT-23")
      )
      (libsource (lib "Transistor_FET_Other") (part "Q_NMOS_Depletion_GSD"))
    )
    (comp (ref "Q45")
      (value "2N7002ET1G")
      (footprint "Package_TO_SOT_SMD:SOT-23")
      (fields
        (field (name "MANUFACTURER PART NUMBER") "2N7002ET1G")
        (field (name "MANUFACTURER") "onsemi")
        (field (name "PACKAGE") "SOT-23")
      )
      (libsource (lib "Transistor_FET_Other") (part "Q_NMOS_Depletion_GSD"))
    )
    (comp (ref "Q46")
      (value "2N7002ET1G")
      (footprint "Package_TO_SOT_SMD:SOT-23")
      (fields
        (field (name "MANUFACTURER PART NUMBER") "2N7002ET1G")
        (field (name "MANUFACTURER") "onsemi")
        (field (name "PACKAGE") "SOT-23")
      )
      (libsource (lib "Transistor_FET_Other") (part "Q_NMOS_Depletion_GSD"))
    )
    (comp (ref "Q47")
      (value "2N7002ET1G")
      (footprint "Package_TO_SOT_SMD:SOT-23")
      (fields
        (field (name "MANUFACTURER PART NUMBER") "2N7002ET1G")
        (field (name "MANUFACTURER") "onsemi")
        (field (name "PACKAGE") "SOT-23")
      )
      (libsource (lib "Transistor_FET_Other") (part "Q_NMOS_Depletion_GSD"))
    )
    (comp (ref "Q48")
      (value "2N7002ET1G")
      (footprint "Package_TO_SOT_SMD:SOT-23")
      (fields
        (field (name "MANUFACTURER PART NUMBER") "2N7002ET1G")
        (field (name "MANUFACTURER") "onsemi")
        (field (name "PACKAGE") "SOT-23")
      )
      (libsource (lib "Transistor_FET_Other") (part "Q_NMOS_Depletion_GSD"))
    )
    (comp (ref "Q49")
      (value "2N7002ET1G")
      (footprint "Package_TO_SOT_SMD:SOT-23")
      (fields
        (field (name "MANUFACTURER PART NUMBER") "2N7002ET1G")
        (field (name "MANUFACTURER") "onsemi")
        (field (name "PACKAGE") "SOT-23")
      )
      (libsource (lib "Transistor_FET_Other") (part "Q_NMOS_Depletion_GSD"))
    )
    (comp (ref "Q50")
      (value "2N7002ET1G")
      (footprint "Package_TO_SOT_SMD:SOT-23")
      (fields
        (field (name "MANUFACTURER PART NUMBER") "2N7002ET1G")
        (field (name "MANUFACTURER") "onsemi")
        (field (name "PACKAGE") "SOT-23")
      )
      (libsource (lib "Transistor_FET_Other") (part "Q_NMOS_Depletion_GSD"))
    )
    (comp (ref "Q51")
      (value "2N7002ET1G")
      (footprint "Package_TO_SOT_SMD:SOT-23")
      (fields
        (field (name "MANUFACTURER PART NUMBER") "2N7002ET1G")
        (field (name "MANUFACTURER") "onsemi")
        (field (name "PACKAGE") "SOT-23")
      )
      (libsource (lib "Transistor_FET_Other") (part "Q_NMOS_Depletion_GSD"))
    )
    (comp (ref "Q52")
      (value "2N7002ET1G")
      (footprint "Package_TO_SOT_SMD:SOT-23")
      (fields
        (field (name "MANUFACTURER PART NUMBER") "2N7002ET1G")
        (field (name "MANUFACTURER") "onsemi")
        (field (name "PACKAGE") "SOT-23")
      )
      (libsource (lib "Transistor_FET_Other") (part "Q_NMOS_Depletion_GSD"))
    )
    (comp (ref "Q53")
      (value "2N7002ET1G")
      (footprint "Package_TO_SOT_SMD:SOT-23")
      (fields
        (field (name "MANUFACTURER PART NUMBER") "2N7002ET1G")
        (field (name "MANUFACTURER") "onsemi")
        (field (name "PACKAGE") "SOT-23")
      )
      (libsource (lib "Transistor_FET_Other") (part "Q_NMOS_Depletion_GSD"))
    )
    (comp (ref "Q54")
      (value "2N7002ET1G")
      (footprint "Package_TO_SOT_SMD:SOT-23")
      (fields
        (field (name "MANUFACTURER PART NUMBER") "2N7002ET1G")
        (field (name "MANUFACTURER") "onsemi")
        (field (name "PACKAGE") "SOT-23")
      )
      (libsource (lib "Transistor_FET_Other") (part "Q_NMOS_Depletion_GSD"))
    )
    (comp (ref "Q55")
      (value "2N7002ET1G")
      (footprint "Package_TO_SOT_SMD:SOT-23")
      (fields
        (field (name "MANUFACTURER PART NUMBER") "2N7002ET1G")
        (field (name "MANUFACTURER") "onsemi")
        (field (name "PACKAGE") "SOT-23")
      )
      (libsource (lib "Transistor_FET_Other") (part "Q_NMOS_Depletion_GSD"))
    )
    (comp (ref "Q56")
      (value "2N7002ET1G")
      (footprint "Package_TO_SOT_SMD:SOT-23")
      (fields
        (field (name "MANUFACTURER PART NUMBER") "2N7002ET1G")
        (field (name "MANUFACTURER") "onsemi")
        (field (name "PACKAGE") "SOT-23")
      )
      (libsource (lib "Transistor_FET_Other") (part "Q_NMOS_Depletion_GSD"))
    )
    (comp (ref "Q57")
      (value "2N7002ET1G")
      (footprint "Package_TO_SOT_SMD:SOT-23")
      (fields
        (field (name "MANUFACTURER PART NUMBER") "2N7002ET1G")
        (field (name "MANUFACTURER") "onsemi")
        (field (name "PACKAGE") "SOT-23")
      )
      (libsource (lib "Transistor_FET_Other") (part "Q_NMOS_Depletion_GSD"))
    )
    (comp (ref "Q58")
      (value "2N7002ET1G")
      (footprint "Package_TO_SOT_SMD:SOT-23")
      (fields
        (field (name "MANUFACTURER PART NUMBER") "2N7002ET1G")
        (field (name "MANUFACTURER") "onsemi")
        (field (name "PACKAGE") "SOT-23")
      )
      (libsource (lib "Transistor_FET_Other") (part "Q_NMOS_Depletion_GSD"))
    )
    (comp (ref "Q59")
      (value "2N7002ET1G")
      (footprint "Package_TO_SOT_SMD:SOT-23")
      (fields
        (field (name "MANUFACTURER PART NUMBER") "2N7002ET1G")
        (field (name "MANUFACTURER") "onsemi")
        (field (name "PACKAGE") "SOT-23")
      )
      (libsource (lib "Transistor_FET_Other") (part "Q_NMOS_Depletion_GSD"))
    )
    (comp (ref "Q60")
      (value "2N7002ET1G")
      (footprint "Package_TO_SOT_SMD:SOT-23")
      (fields
        (field (name "MANUFACTURER PART NUMBER") "2N7002ET1G")
        (field (name "MANUFACTURER") "onsemi")
        (field (name "PACKAGE") "SOT-23")
      )
      (libsource (lib "Transistor_FET_Other") (part "Q_NMOS_Depletion_GSD"))
    )
    (comp (ref "Q61")
      (value "2N7002ET1G")
      (footprint "Package_TO_SOT_SMD:SOT-23")
      (fields
        (field (name "MANUFACTURER PART NUMBER") "2N7002ET1G")
        (field (name "MANUFACTURER") "onsemi")
        (field (name "PACKAGE") "SOT-23")
      )
      (libsource (lib "Transistor_FET_Other") (part "Q_NMOS_Depletion_GSD"))
    )
    (comp (ref "Q62")
      (value "2N7002ET1G")
      (footprint "Package_TO_SOT_SMD:SOT-23")
      (fields
        (field (name "MANUFACTURER PART NUMBER") "2N7002ET1G")
        (field (name "MANUFACTURER") "onsemi")
        (field (name "PACKAGE") "SOT-23")
      )
      (libsource (lib "Transistor_FET_Other") (part "Q_NMOS_Depletion_GSD"))
    )
    (comp (ref "Q63")
      (value "2N7002ET1G")
      (footprint "Package_TO_SOT_SMD:SOT-23")
      (fields
        (field (name "MANUFACTURER PART NUMBER") "2N7002ET1G")
        (field (name "MANUFACTURER") "onsemi")
        (field (name "PACKAGE") "SOT-23")
      )
      (libsource (lib "Transistor_FET_Other") (part "Q_NMOS_Depletion_GSD"))
    )
    (comp (ref "Q64")
      (value "2N7002ET1G")
      (footprint "Package_TO_SOT_SMD:SOT-23")
      (fields
        (field (name "MANUFACTURER PART NUMBER") "2N7002ET1G")
        (field (name "MANUFACTURER") "onsemi")
        (field (name "PACKAGE") "SOT-23")
      )
      (libsource (lib "Transistor_FET_Other") (part "Q_NMOS_Depletion_GSD"))
    )
    (comp (ref "R32")
      (value "10K")
      (footprint "Resistor_SMD:R_0603_1608Metric")
      (fields
        (field (name "MANUFACTURER PART NUMBER") "FRC0603J103TS")
        (field (name "MANUFACTURER") "FOJAN")
        (field (name "PACKAGE") "R_0603")
      )
      (libsource (lib "Device") (part "R_US"))
    )
    (comp (ref "R33")
      (value "1K")
      (footprint "Resistor_SMD:R_0603_1608Metric")
      (fields
        (field (name "MANUFACTURER PART NUMBER") "RC0603JR-071KL")
        (field (name "MANUFACTURER") "YAGEO")
        (field (name "PACKAGE") "R_0603")
      )
      (libsource (lib "Device") (part "R_US"))
    )
    (comp (ref "R34")
      (value "1K")
      (footprint "Resistor_SMD:R_0603_1608Metric")
      (fields
        (field (name "MANUFACTURER PART NUMBER") "RC0603JR-071KL")
        (field (name "MANUFACTURER") "YAGEO")
        (field (name "PACKAGE") "R_0603")
      )
      (libsource (lib "Device") (part "R_US"))
    )
    (comp (ref "R35")
      (value "10K")
      (footprint "Resistor_SMD:R_0603_1608Metric")
      (fields
        (field (name "MANUFACTURER PART NUMBER") "FRC0603J103TS")
        (field (name "MANUFACTURER") "FOJAN")
        (field (name "PACKAGE") "R_0603")
      )
      (libsource (lib "Device") (part "R_US"))
    )
    (comp (ref "R56")
      (value "1K")
      (footprint "Resistor_SMD:R_0603_1608Metric")
      (fields
        (field (name "MANUFACTURER PART NUMBER") "RC0603JR-071KL")
        (field (name "MANUFACTURER") "YAGEO")
        (field (name "PACKAGE") "R_0603")
      )
      (libsource (lib "Device") (part "R_US"))
    )
    (comp (ref "R57")
      (value "1K")
      (footprint "Resistor_SMD:R_0603_1608Metric")
      (fields
        (field (name "MANUFACTURER PART NUMBER") "RC0603JR-071KL")
        (field (name "MANUFACTURER") "YAGEO")
        (field (name "PACKAGE") "R_0603")
      )
      (libsource (lib "Device") (part "R_US"))
    )
    (comp (ref "R58")
      (value "10K")
      (footprint "Resistor_SMD:R_0603_1608Metric")
      (fields
        (field (name "MANUFACTURER PART NUMBER") "FRC0603J103TS")
        (field (name "MANUFACTURER") "FOJAN")
        (field (name "PACKAGE") "R_0603")
      )
      (libsource (lib "Device") (part "R_US"))
    )
    (comp (ref "R59")
      (value "10K")
      (footprint "Resistor_SMD:R_0603_1608Metric")
      (fields
        (field (name "MANUFACTURER PART NUMBER") "FRC0603J103TS")
        (field (name "MANUFACTURER") "FOJAN")
        (field (name "PACKAGE") "R_0603")
      )
      (libsource (lib "Device") (part "R_US"))
    )
    (comp (ref "R60")
      (value "1K")
      (footprint "Resistor_SMD:R_0603_1608Metric")
      (fields
        (field (name "MANUFACTURER PART NUMBER") "RC0603JR-071KL")
        (field (name "MANUFACTURER") "YAGEO")
        (field (name "PACKAGE") "R_0603")
      )
      (libsource (lib "Device") (part "R_US"))
    )
    (comp (ref "R61")
      (value "1K")
      (footprint "Resistor_SMD:R_0603_1608Metric")
      (fields
        (field (name "MANUFACTURER PART NUMBER") "RC0603JR-071KL")
        (field (name "MANUFACTURER") "YAGEO")
        (field (name "PACKAGE") "R_0603")
      )
      (libsource (lib "Device") (part "R_US"))
    )
    (comp (ref "R62")
      (value "10K")
      (footprint "Resistor_SMD:R_0603_1608Metric")
      (fields
        (field (name "MANUFACTURER PART NUMBER") "FRC0603J103TS")
        (field (name "MANUFACTURER") "FOJAN")
        (field (name "PACKAGE") "R_0603")
      )
      (libsource (lib "Device") (part "R_US"))
    )
    (comp (ref "R63")
      (value "10K")
      (footprint "Resistor_SMD:R_0603_1608Metric")
      (fields
        (field (name "MANUFACTURER PART NUMBER") "FRC0603J103TS")
        (field (name "MANUFACTURER") "FOJAN")
        (field (name "PACKAGE") "R_0603")
      )
      (libsource (lib "Device") (part "R_US"))
    )
    (comp (ref "R64")
      (value "1K")
      (footprint "Resistor_SMD:R_0603_1608Metric")
      (fields
        (field (name "MANUFACTURER PART NUMBER") "RC0603JR-071KL")
        (field (name "MANUFACTURER") "YAGEO")
        (field (name "PACKAGE") "R_0603")
      )
      (libsource (lib "Device") (part "R_US"))
    )
    (comp (ref "R65")
      (value "1K")
      (footprint "Resistor_SMD:R_0603_1608Metric")
      (fields
        (field (name "MANUFACTURER PART NUMBER") "RC0603JR-071KL")
        (field (name "MANUFACTURER") "YAGEO")
        (field (name "PACKAGE") "R_0603")
      )
      (libsource (lib "Device") (part "R_US"))
    )
    (comp (ref "R66")
      (value "10K")
      (footprint "Resistor_SMD:R_0603_1608Metric")
      (fields
        (field (name "MANUFACTURER PART NUMBER") "FRC0603J103TS")
        (field (name "MANUFACTURER") "FOJAN")
        (field (name "PACKAGE") "R_0603")
      )
      (libsource (lib "Device") (part "R_US"))
    )
    (comp (ref "R67")
      (value "10K")
      (footprint "Resistor_SMD:R_0603_1608Metric")
      (fields
        (field (name "MANUFACTURER PART NUMBER") "FRC0603J103TS")
        (field (name "MANUFACTURER") "FOJAN")
        (field (name "PACKAGE") "R_0603")
      )
      (libsource (lib "Device") (part "R_US"))
    )
    (comp (ref "R68")
      (value "1K")
      (footprint "Resistor_SMD:R_0603_1608Metric")
      (fields
        (field (name "MANUFACTURER PART NUMBER") "RC0603JR-071KL")
        (field (name "MANUFACTURER") "YAGEO")
        (field (name "PACKAGE") "R_0603")
      )
      (libsource (lib "Device") (part "R_US"))
    )
    (comp (ref "R69")
      (value "1K")
      (footprint "Resistor_SMD:R_0603_1608Metric")
      (fields
        (field (name "MANUFACTURER PART NUMBER") "RC0603JR-071KL")
        (field (name "MANUFACTURER") "YAGEO")
        (field (name "PACKAGE") "R_0603")
      )
      (libsource (lib "Device") (part "R_US"))
    )
    (comp (ref "R70")
      (value "10K")
      (footprint "Resistor_SMD:R_0603_1608Metric")
      (fields
        (field (name "MANUFACTURER PART NUMBER") "FRC0603J103TS")
        (field (name "MANUFACTURER") "FOJAN")
        (field (name "PACKAGE") "R_0603")
      )
      (libsource (lib "Device") (part "R_US"))
    )
    (comp (ref "R71")
      (value "10K")
      (footprint "Resistor_SMD:R_0603_1608Metric")
      (fields
        (field (name "MANUFACTURER PART NUMBER") "FRC0603J103TS")
        (field (name "MANUFACTURER") "FOJAN")
        (field (name "PACKAGE") "R_0603")
      )
      (libsource (lib "Device") (part "R_US"))
    )
    (comp (ref "R72")
      (value "1K")
      (footprint "Resistor_SMD:R_0603_1608Metric")
      (fields
        (field (name "MANUFACTURER PART NUMBER") "RC0603JR-071KL")
        (field (name "MANUFACTURER") "YAGEO")
        (field (name "PACKAGE") "R_0603")
      )
      (libsource (lib "Device") (part "R_US"))
    )
    (comp (ref "R73")
      (value "1K")
      (footprint "Resistor_SMD:R_0603_1608Metric")
      (fields
        (field (name "MANUFACTURER PART NUMBER") "RC0603JR-071KL")
        (field (name "MANUFACTURER") "YAGEO")
        (field (name "PACKAGE") "R_0603")
      )
      (libsource (lib "Device") (part "R_US"))
    )
    (comp (ref "R74")
      (value "10K")
      (footprint "Resistor_SMD:R_0603_1608Metric")
      (fields
        (field (name "MANUFACTURER PART NUMBER") "FRC0603J103TS")
        (field (name "MANUFACTURER") "FOJAN")
        (field (name "PACKAGE") "R_0603")
      )
      (libsource (lib "Device") (part "R_US"))
    )
    (comp (ref "R75")
      (value "10K")
      (footprint "Resistor_SMD:R_0603_1608Metric")
      (fields
        (field (name "MANUFACTURER PART NUMBER") "FRC0603J103TS")
        (field (name "MANUFACTURER") "FOJAN")
        (field (name "PACKAGE") "R_0603")
      )
      (libsource (lib "Device") (part "R_US"))
    )
    (comp (ref "R76")
      (value "1K")
      (footprint "Resistor_SMD:R_0603_1608Metric")
      (fields
        (field (name "MANUFACTURER PART NUMBER") "RC0603JR-071KL")
        (field (name "MANUFACTURER") "YAGEO")
        (field (name "PACKAGE") "R_0603")
      )
      (libsource (lib "Device") (part "R_US"))
    )
    (comp (ref "R77")
      (value "1K")
      (footprint "Resistor_SMD:R_0603_1608Metric")
      (fields
        (field (name "MANUFACTURER PART NUMBER") "RC0603JR-071KL")
        (field (name "MANUFACTURER") "YAGEO")
        (field (name "PACKAGE") "R_0603")
      )
      (libsource (lib "Device") (part "R_US"))
    )
    (comp (ref "R78")
      (value "10K")
      (footprint "Resistor_SMD:R_0603_1608Metric")
      (fields
        (field (name "MANUFACTURER PART NUMBER") "FRC0603J103TS")
        (field (name "MANUFACTURER") "FOJAN")
        (field (name "PACKAGE") "R_0603")
      )
      (libsource (lib "Device") (part "R_US"))
    )
    (comp (ref "R79")
      (value "10K")
      (footprint "Resistor_SMD:R_0603_1608Metric")
      (fields
        (field (name "MANUFACTURER PART NUMBER") "FRC0603J103TS")
        (field (name "MANUFACTURER") "FOJAN")
        (field (name "PACKAGE") "R_0603")
      )
      (libsource (lib "Device") (part "R_US"))
    )
    (comp (ref "R80")
      (value "1K")
      (footprint "Resistor_SMD:R_0603_1608Metric")
      (fields
        (field (name "MANUFACTURER PART NUMBER") "RC0603JR-071KL")
        (field (name "MANUFACTURER") "YAGEO")
        (field (name "PACKAGE") "R_0603")
      )
      (libsource (lib "Device") (part "R_US"))
    )
    (comp (ref "R81")
      (value "1K")
      (footprint "Resistor_SMD:R_0603_1608Metric")
      (fields
        (field (name "MANUFACTURER PART NUMBER") "RC0603JR-071KL")
        (field (name "MANUFACTURER") "YAGEO")
        (field (name "PACKAGE") "R_0603")
      )
      (libsource (lib "Device") (part "R_US"))
    )
    (comp (ref "R82")
      (value "10K")
      (footprint "Resistor_SMD:R_0603_1608Metric")
      (fields
        (field (name "MANUFACTURER PART NUMBER") "FRC0603J103TS")
        (field (name "MANUFACTURER") "FOJAN")
        (field (name "PACKAGE") "R_0603")
      )
      (libsource (lib "Device") (part "R_US"))
    )
    (comp (ref "R83")
      (value "10K")
      (footprint "Resistor_SMD:R_0603_1608Metric")
      (fields
        (field (name "MANUFACTURER PART NUMBER") "FRC0603J103TS")
        (field (name "MANUFACTURER") "FOJAN")
        (field (name "PACKAGE") "R_0603")
      )
      (libsource (lib "Device") (part "R_US"))
    )
    (comp (ref "R91")
      (value "1K")
      (footprint "Resistor_SMD:R_0603_1608Metric")
      (fields
        (field (name "MANUFACTURER PART NUMBER") "RC0603JR-071KL")
        (field (name "MANUFACTURER") "YAGEO")
        (field (name "PACKAGE") "R_0603")
      )
      (libsource (lib "Device") (part "R_US"))
    )
    (comp (ref "R92")
      (value "1K")
      (footprint "Resistor_SMD:R_0603_1608Metric")
      (fields
        (field (name "MANUFACTURER PART NUMBER") "RC0603JR-071KL")
        (field (name "MANUFACTURER") "YAGEO")
        (field (name "PACKAGE") "R_0603")
      )
      (libsource (lib "Device") (part "R_US"))
    )
    (comp (ref "R93")
      (value "1K")
      (footprint "Resistor_SMD:R_0603_1608Metric")
      (fields
        (field (name "MANUFACTURER PART NUMBER") "RC0603JR-071KL")
        (field (name "MANUFACTURER") "YAGEO")
        (field (name "PACKAGE") "R_0603")
      )
      (libsource (lib "Device") (part "R_US"))
    )
    (comp (ref "R94")
      (value "1K")
      (footprint "Resistor_SMD:R_0603_1608Metric")
      (fields
        (field (name "MANUFACTURER PART NUMBER") "RC0603JR-071KL")
        (field (name "MANUFACTURER") "YAGEO")
        (field (name "PACKAGE") "R_0603")
      )
      (libsource (lib "Device") (part "R_US"))
    )
    (comp (ref "R95")
      (value "10K")
      (footprint "Resistor_SMD:R_0603_1608Metric")
      (fields
        (field (name "MANUFACTURER PART NUMBER") "FRC0603J103TS")
        (field (name "MANUFACTURER") "FOJAN")
        (field (name "PACKAGE") "R_0603")
      )
      (libsource (lib "Device") (part "R_US"))
    )
    (comp (ref "R96")
      (value "10K")
      (footprint "Resistor_SMD:R_0603_1608Metric")
      (fields
        (field (name "MANUFACTURER PART NUMBER") "FRC0603J103TS")
        (field (name "MANUFACTURER") "FOJAN")
        (field (name "PACKAGE") "R_0603")
      )
      (libsource (lib "Device") (part "R_US"))
    )
    (comp (ref "R97")
      (value "10K")
      (footprint "Resistor_SMD:R_0603_1608Metric")
      (fields
        (field (name "MANUFACTURER PART NUMBER") "FRC0603J103TS")
        (field (name "MANUFACTURER") "FOJAN")
        (field (name "PACKAGE") "R_0603")
      )
      (libsource (lib "Device") (part "R_US"))
    )
    (comp (ref "R98")
      (value "10K")
      (footprint "Resistor_SMD:R_0603_1608Metric")
      (fields
        (field (name "MANUFACTURER PART NUMBER") "FRC0603J103TS")
        (field (name "MANUFACTURER") "FOJAN")
        (field (name "PACKAGE") "R_0603")
      )
      (libsource (lib "Device") (part "R_US"))
    )
    (comp (ref "R99")
      (value "1K")
      (footprint "Resistor_SMD:R_0603_1608Metric")
      (fields
        (field (name "MANUFACTURER PART NUMBER") "RC0603JR-071KL")
        (field (name "MANUFACTURER") "YAGEO")
        (field (name "PACKAGE") "R_0603")
      )
      (libsource (lib "Device") (part "R_US"))
    )
    (comp (ref "R100")
      (value "1K")
      (footprint "Resistor_SMD:R_0603_1608Metric")
      (fields
        (field (name "MANUFACTURER PART NUMBER") "RC0603JR-071KL")
        (field (name "MANUFACTURER") "YAGEO")
        (field (name "PACKAGE") "R_0603")
      )
      (libsource (lib "Device") (part "R_US"))
    )
    (comp (ref "R101")
      (value "10K")
      (footprint "Resistor_SMD:R_0603_1608Metric")
      (fields
        (field (name "MANUFACTURER PART NUMBER") "FRC0603J103TS")
        (field (name "MANUFACTURER") "FOJAN")
        (field (name "PACKAGE") "R_0603")
      )
      (libsource (lib "Device") (part "R_US"))
    )
    (comp (ref "R102")
      (value "10K")
      (footprint "Resistor_SMD:R_0603_1608Metric")
      (fields
        (field (name "MANUFACTURER PART NUMBER") "FRC0603J103TS")
        (field (name "MANUFACTURER") "FOJAN")
        (field (name "PACKAGE") "R_0603")
      )
      (libsource (lib "Device") (part "R_US"))
    )
    (comp (ref "R103")
      (value "1K")
      (footprint "Resistor_SMD:R_0603_1608Metric")
      (fields
        (field (name "MANUFACTURER PART NUMBER") "RC0603JR-071KL")
        (field (name "MANUFACTURER") "YAGEO")
        (field (name "PACKAGE") "R_0603")
      )
      (libsource (lib "Device") (part "R_US"))
    )
    (comp (ref "R104")
      (value "1K")
      (footprint "Resistor_SMD:R_0603_1608Metric")
      (fields
        (field (name "MANUFACTURER PART NUMBER") "RC0603JR-071KL")
        (field (name "MANUFACTURER") "YAGEO")
        (field (name "PACKAGE") "R_0603")
      )
      (libsource (lib "Device") (part "R_US"))
    )
    (comp (ref "R105")
      (value "10K")
      (footprint "Resistor_SMD:R_0603_1608Metric")
      (fields
        (field (name "MANUFACTURER PART NUMBER") "FRC0603J103TS")
        (field (name "MANUFACTURER") "FOJAN")
        (field (name "PACKAGE") "R_0603")
      )
      (libsource (lib "Device") (part "R_US"))
    )
    (comp (ref "R106")
      (value "10K")
      (footprint "Resistor_SMD:R_0603_1608Metric")
      (fields
        (field (name "MANUFACTURER PART NUMBER") "FRC0603J103TS")
        (field (name "MANUFACTURER") "FOJAN")
        (field (name "PACKAGE") "R_0603")
      )
      (libsource (lib "Device") (part "R_US"))
    )
    (comp (ref "R107")
      (value "1K")
      (footprint "Resistor_SMD:R_0603_1608Metric")
      (fields
        (field (name "MANUFACTURER PART NUMBER") "RC0603JR-071KL")
        (field (name "MANUFACTURER") "YAGEO")
        (field (name "PACKAGE") "R_0603")
      )
      (libsource (lib "Device") (part "R_US"))
    )
    (comp (ref "R108")
      (value "1K")
      (footprint "Resistor_SMD:R_0603_1608Metric")
      (fields
        (field (name "MANUFACTURER PART NUMBER") "RC0603JR-071KL")
        (field (name "MANUFACTURER") "YAGEO")
        (field (name "PACKAGE") "R_0603")
      )
      (libsource (lib "Device") (part "R_US"))
    )
    (comp (ref "R109")
      (value "10K")
      (footprint "Resistor_SMD:R_0603_1608Metric")
      (fields
        (field (name "MANUFACTURER PART NUMBER") "FRC0603J103TS")
        (field (name "MANUFACTURER") "FOJAN")
        (field (name "PACKAGE") "R_0603")
      )
      (libsource (lib "Device") (part "R_US"))
    )
    (comp (ref "R110")
      (value "10K")
      (footprint "Resistor_SMD:R_0603_1608Metric")
      (fields
        (field (name "MANUFACTURER PART NUMBER") "FRC0603J103TS")
        (field (name "MANUFACTURER") "FOJAN")
        (field (name "PACKAGE") "R_0603")
      )
      (libsource (lib "Device") (part "R_US"))
    )
    (comp (ref "R111")
      (value "1K")
      (footprint "Resistor_SMD:R_0603_1608Metric")
      (fields
        (field (name "MANUFACTURER PART NUMBER") "RC0603JR-071KL")
        (field (name "MANUFACTURER") "YAGEO")
        (field (name "PACKAGE") "R_0603")
      )
      (libsource (lib "Device") (part "R_US"))
    )
    (comp (ref "R112")
      (value "1K")
      (footprint "Resistor_SMD:R_0603_1608Metric")
      (fields
        (field (name "MANUFACTURER PART NUMBER") "RC0603JR-071KL")
        (field (name "MANUFACTURER") "YAGEO")
        (field (name "PACKAGE") "R_0603")
      )
      (libsource (lib "Device") (part "R_US"))
    )
    (comp (ref "R113")
      (value "10K")
      (footprint "Resistor_SMD:R_0603_1608Metric")
      (fields
        (field (name "MANUFACTURER PART NUMBER") "FRC0603J103TS")
        (field (name "MANUFACTURER") "FOJAN")
        (field (name "PACKAGE") "R_0603")
      )
      (libsource (lib "Device") (part "R_US"))
    )
    (comp (ref "R114")
      (value "10K")
      (footprint "Resistor_SMD:R_0603_1608Metric")
      (fields
        (field (name "MANUFACTURER PART NUMBER") "FRC0603J103TS")
        (field (name "MANUFACTURER") "FOJAN")
        (field (name "PACKAGE") "R_0603")
      )
      (libsource (lib "Device") (part "R_US"))
    )
    (comp (ref "R115")
      (value "1K")
      (footprint "Resistor_SMD:R_0603_1608Metric")
      (fields
        (field (name "MANUFACTURER PART NUMBER") "RC0603JR-071KL")
        (field (name "MANUFACTURER") "YAGEO")
        (field (name "PACKAGE") "R_0603")
      )
      (libsource (lib "Device") (part "R_US"))
    )
    (comp (ref "R116")
      (value "1K")
      (footprint "Resistor_SMD:R_0603_1608Metric")
      (fields
        (field (name "MANUFACTURER PART NUMBER") "RC0603JR-071KL")
        (field (name "MANUFACTURER") "YAGEO")
        (field (name "PACKAGE") "R_0603")
      )
      (libsource (lib "Device") (part "R_US"))
    )
    (comp (ref "R117")
      (value "10K")
      (footprint "Resistor_SMD:R_0603_1608Metric")
      (fields
        (field (name "MANUFACTURER PART NUMBER") "FRC0603J103TS")
        (field (name "MANUFACTURER") "FOJAN")
        (field (name "PACKAGE") "R_0603")
      )
      (libsource (lib "Device") (part "R_US"))
    )
    (comp (ref "R118")
      (value "10K")
      (footprint "Resistor_SMD:R_0603_1608Metric")
      (fields
        (field (name "MANUFACTURER PART NUMBER") "FRC0603J103TS")
        (field (name "MANUFACTURER") "FOJAN")
        (field (name "PACKAGE") "R_0603")
      )
      (libsource (lib "Device") (part "R_US"))
    )
    (comp (ref "R119")
      (value "1K")
      (footprint "Resistor_SMD:R_0603_1608Metric")
      (fields
        (field (name "MANUFACTURER PART NUMBER") "RC0603JR-071KL")
        (field (name "MANUFACTURER") "YAGEO")
        (field (name "PACKAGE") "R_0603")
      )
      (libsource (lib "Device") (part "R_US"))
    )
    (comp (ref "R120")
      (value "1K")
      (footprint "Resistor_SMD:R_0603_1608Metric")
      (fields
        (field (name "MANUFACTURER PART NUMBER") "RC0603JR-071KL")
        (field (name "MANUFACTURER") "YAGEO")
        (field (name "PACKAGE") "R_0603")
      )
      (libsource (lib "Device") (part "R_US"))
    )
    (comp (ref "R121")
      (value "10K")
      (footprint "Resistor_SMD:R_0603_1608Metric")
      (fields
        (field (name "MANUFACTURER PART NUMBER") "FRC0603J103TS")
        (field (name "MANUFACTURER") "FOJAN")
        (field (name "PACKAGE") "R_0603")
      )
      (libsource (lib "Device") (part "R_US"))
    )
    (comp (ref "R122")
      (value "10K")
      (footprint "Resistor_SMD:R_0603_1608Metric")
      (fields
        (field (name "MANUFACTURER PART NUMBER") "FRC0603J103TS")
        (field (name "MANUFACTURER") "FOJAN")
        (field (name "PACKAGE") "R_0603")
      )
      (libsource (lib "Device") (part "R_US"))
    )
    (comp (ref "R123")
      (value "1K")
      (footprint "Resistor_SMD:R_0603_1608Metric")
      (fields
        (field (name "MANUFACTURER PART NUMBER") "RC0603JR-071KL")
        (field (name "MANUFACTURER") "YAGEO")
        (field (name "PACKAGE") "R_0603")
      )
      (libsource (lib "Device") (part "R_US"))
    )
    (comp (ref "R124")
      (value "1K")
      (footprint "Resistor_SMD:R_0603_1608Metric")
      (fields
        (field (name "MANUFACTURER PART NUMBER") "RC0603JR-071KL")
        (field (name "MANUFACTURER") "YAGEO")
        (field (name "PACKAGE") "R_0603")
      )
      (libsource (lib "Device") (part "R_US"))
    )
    (comp (ref "R125")
      (value "10K")
      (footprint "Resistor_SMD:R_0603_1608Metric")
      (fields
        (field (name "MANUFACTURER PART NUMBER") "FRC0603J103TS")
        (field (name "MANUFACTURER") "FOJAN")
        (field (name "PACKAGE") "R_0603")
      )
      (libsource (lib "Device") (part "R_US"))
    )
    (comp (ref "R126")
      (value "10K")
      (footprint "Resistor_SMD:R_0603_1608Metric")
      (fields
        (field (name "MANUFACTURER PART NUMBER") "FRC0603J103TS")
        (field (name "MANUFACTURER") "FOJAN")
        (field (name "PACKAGE") "R_0603")
      )
      (libsource (lib "Device") (part "R_US"))
    )
    (comp (ref "R127")
      (value "1K")
      (footprint "Resistor_SMD:R_0603_1608Metric")
      (fields
        (field (name "MANUFACTURER PART NUMBER") "RC0603JR-071KL")
        (field (name "MANUFACTURER") "YAGEO")
        (field (name "PACKAGE") "R_0603")
      )
      (libsource (lib "Device") (part "R_US"))
    )
    (comp (ref "R128")
      (value "1K")
      (footprint "Resistor_SMD:R_0603_1608Metric")
      (fields
        (field (name "MANUFACTURER PART NUMBER") "RC0603JR-071KL")
        (field (name "MANUFACTURER") "YAGEO")
        (field (name "PACKAGE") "R_0603")
      )
      (libsource (lib "Device") (part "R_US"))
    )
    (comp (ref "R129")
      (value "10K")
      (footprint "Resistor_SMD:R_0603_1608Metric")
      (fields
        (field (name "MANUFACTURER PART NUMBER") "FRC0603J103TS")
        (field (name "MANUFACTURER") "FOJAN")
        (field (name "PACKAGE") "R_0603")
      )
      (libsource (lib "Device") (part "R_US"))
    )
    (comp (ref "R130")
      (value "10K")
      (footprint "Resistor_SMD:R_0603_1608Metric")
      (fields
        (field (name "MANUFACTURER PART NUMBER") "FRC0603J103TS")
        (field (name "MANUFACTURER") "FOJAN")
        (field (name "PACKAGE") "R_0603")
      )
      (libsource (lib "Device") (part "R_US"))
    )
    (comp (ref "R131")
      (value "1K")
      (footprint "Resistor_SMD:R_0603_1608Metric")
      (fields
        (field (name "MANUFACTURER PART NUMBER") "RC0603JR-071KL")
        (field (name "MANUFACTURER") "YAGEO")
        (field (name "PACKAGE") "R_0603")
      )
      (libsource (lib "Device") (part "R_US"))
    )
    (comp (ref "R132")
      (value "1K")
      (footprint "Resistor_SMD:R_0603_1608Metric")
      (fields
        (field (name "MANUFACTURER PART NUMBER") "RC0603JR-071KL")
        (field (name "MANUFACTURER") "YAGEO")
        (field (name "PACKAGE") "R_0603")
      )
      (libsource (lib "Device") (part "R_US"))
    )
    (comp (ref "R133")
      (value "10K")
      (footprint "Resistor_SMD:R_0603_1608Metric")
      (fields
        (field (name "MANUFACTURER PART NUMBER") "FRC0603J103TS")
        (field (name "MANUFACTURER") "FOJAN")
        (field (name "PACKAGE") "R_0603")
      )
      (libsource (lib "Device") (part "R_US"))
    )
    (comp (ref "R134")
      (value "10K")
      (footprint "Resistor_SMD:R_0603_1608Metric")
      (fields
        (field (name "MANUFACTURER PART NUMBER") "FRC0603J103TS")
        (field (name "MANUFACTURER") "FOJAN")
        (field (name "PACKAGE") "R_0603")
      )
      (libsource (lib "Device") (part "R_US"))
    )
    (comp (ref "R135")
      (value "1K")
      (footprint "Resistor_SMD:R_0603_1608Metric")
      (fields
        (field (name "MANUFACTURER PART NUMBER") "RC0603JR-071KL")
        (field (name "MANUFACTURER") "YAGEO")
        (field (name "PACKAGE") "R_0603")
      )
      (libsource (lib "Device") (part "R_US"))
    )
    (comp (ref "R136")
      (value "1K")
      (footprint "Resistor_SMD:R_0603_1608Metric")
      (fields
        (field (name "MANUFACTURER PART NUMBER") "RC0603JR-071KL")
        (field (name "MANUFACTURER") "YAGEO")
        (field (name "PACKAGE") "R_0603")
      )
      (libsource (lib "Device") (part "R_US"))
    )
    (comp (ref "R137")
      (value "10K")
      (footprint "Resistor_SMD:R_0603_1608Metric")
      (fields
        (field (name "MANUFACTURER PART NUMBER") "FRC0603J103TS")
        (field (name "MANUFACTURER") "FOJAN")
        (field (name "PACKAGE") "R_0603")
      )
      (libsource (lib "Device") (part "R_US"))
    )
    (comp (ref "R138")
      (value "10K")
      (footprint "Resistor_SMD:R_0603_1608Metric")
      (fields
        (field (name "MANUFACTURER PART NUMBER") "FRC0603J103TS")
        (field (name "MANUFACTURER") "FOJAN")
        (field (name "PACKAGE") "R_0603")
      )
      (libsource (lib "Device") (part "R_US"))
    )
    (comp (ref "R139")
      (value "1K")
      (footprint "Resistor_SMD:R_0603_1608Metric")
      (fields
        (field (name "MANUFACTURER PART NUMBER") "RC0603JR-071KL")
        (field (name "MANUFACTURER") "YAGEO")
        (field (name "PACKAGE") "R_0603")
      )
      (libsource (lib "Device") (part "R_US"))
    )
    (comp (ref "R140")
      (value "1K")
      (footprint "Resistor_SMD:R_0603_1608Metric")
      (fields
        (field (name "MANUFACTURER PART NUMBER") "RC0603JR-071KL")
        (field (name "MANUFACTURER") "YAGEO")
        (field (name "PACKAGE") "R_0603")
      )
      (libsource (lib "Device") (part "R_US"))
    )
    (comp (ref "R141")
      (value "10K")
      (footprint "Resistor_SMD:R_0603_1608Metric")
      (fields
        (field (name "MANUFACTURER PART NUMBER") "FRC0603J103TS")
        (field (name "MANUFACTURER") "FOJAN")
        (field (name "PACKAGE") "R_0603")
      )
      (libsource (lib "Device") (part "R_US"))
    )
    (comp (ref "R142")
      (value "10K")
      (footprint "Resistor_SMD:R_0603_1608Metric")
      (fields
        (field (name "MANUFACTURER PART NUMBER") "FRC0603J103TS")
        (field (name "MANUFACTURER") "FOJAN")
        (field (name "PACKAGE") "R_0603")
      )
      (libsource (lib "Device") (part "R_US"))
    )
    (comp (ref "R143")
      (value "1K")
      (footprint "Resistor_SMD:R_0603_1608Metric")
      (fields
        (field (name "MANUFACTURER PART NUMBER") "RC0603JR-071KL")
        (field (name "MANUFACTURER") "YAGEO")
        (field (name "PACKAGE") "R_0603")
      )
      (libsource (lib "Device") (part "R_US"))
    )
    (comp (ref "R144")
      (value "1K")
      (footprint "Resistor_SMD:R_0603_1608Metric")
      (fields
        (field (name "MANUFACTURER PART NUMBER") "RC0603JR-071KL")
        (field (name "MANUFACTURER") "YAGEO")
        (field (name "PACKAGE") "R_0603")
      )
      (libsource (lib "Device") (part "R_US"))
    )
    (comp (ref "R145")
      (value "10K")
      (footprint "Resistor_SMD:R_0603_1608Metric")
      (fields
        (field (name "MANUFACTURER PART NUMBER") "FRC0603J103TS")
        (field (name "MANUFACTURER") "FOJAN")
        (field (name "PACKAGE") "R_0603")
      )
      (libsource (lib "Device") (part "R_US"))
    )
    (comp (ref "R146")
      (value "10K")
      (footprint "Resistor_SMD:R_0603_1608Metric")
      (fields
        (field (name "MANUFACTURER PART NUMBER") "FRC0603J103TS")
        (field (name "MANUFACTURER") "FOJAN")
        (field (name "PACKAGE") "R_0603")
      )
      (libsource (lib "Device") (part "R_US"))
    )
    (comp (ref "R147")
      (value "1K")
      (footprint "Resistor_SMD:R_0603_1608Metric")
      (fields
        (field (name "MANUFACTURER PART NUMBER") "RC0603JR-071KL")
        (field (name "MANUFACTURER") "YAGEO")
        (field (name "PACKAGE") "R_0603")
      )
      (libsource (lib "Device") (part "R_US"))
    )
    (comp (ref "R148")
      (value "1K")
      (footprint "Resistor_SMD:R_0603_1608Metric")
      (fields
        (field (name "MANUFACTURER PART NUMBER") "RC0603JR-071KL")
        (field (name "MANUFACTURER") "YAGEO")
        (field (name "PACKAGE") "R_0603")
      )
      (libsource (lib "Device") (part "R_US"))
    )
    (comp (ref "R149")
      (value "10K")
      (footprint "Resistor_SMD:R_0603_1608Metric")
      (fields
        (field (name "MANUFACTURER PART NUMBER") "FRC0603J103TS")
        (field (name "MANUFACTURER") "FOJAN")
        (field (name "PACKAGE") "R_0603")
      )
      (libsource (lib "Device") (part "R_US"))
    )
    (comp (ref "R150")
      (value "10K")
      (footprint "Resistor_SMD:R_0603_1608Metric")
      (fields
        (field (name "MANUFACTURER PART NUMBER") "FRC0603J103TS")
        (field (name "MANUFACTURER") "FOJAN")
        (field (name "PACKAGE") "R_0603")
      )
      (libsource (lib "Device") (part "R_US"))
    )
    (comp (ref "R151")
      (value "1K")
      (footprint "Resistor_SMD:R_0603_1608Metric")
      (fields
        (field (name "MANUFACTURER PART NUMBER") "RC0603JR-071KL")
        (field (name "MANUFACTURER") "YAGEO")
        (field (name "PACKAGE") "R_0603")
      )
      (libsource (lib "Device") (part "R_US"))
    )
    (comp (ref "R152")
      (value "1K")
      (footprint "Resistor_SMD:R_0603_1608Metric")
      (fields
        (field (name "MANUFACTURER PART NUMBER") "RC0603JR-071KL")
        (field (name "MANUFACTURER") "YAGEO")
        (field (name "PACKAGE") "R_0603")
      )
      (libsource (lib "Device") (part "R_US"))
    )
    (comp (ref "R153")
      (value "10K")
      (footprint "Resistor_SMD:R_0603_1608Metric")
      (fields
        (field (name "MANUFACTURER PART NUMBER") "FRC0603J103TS")
        (field (name "MANUFACTURER") "FOJAN")
        (field (name "PACKAGE") "R_0603")
      )
      (libsource (lib "Device") (part "R_US"))
    )
    (comp (ref "R154")
      (value "10K")
      (footprint "Resistor_SMD:R_0603_1608Metric")
      (fields
        (field (name "MANUFACTURER PART NUMBER") "FRC0603J103TS")
        (field (name "MANUFACTURER") "FOJAN")
        (field (name "PACKAGE") "R_0603")
      )
      (libsource (lib "Device") (part "R_US"))
    )
  )
  (nets
    (net (code "1") (name "+12V") (class "Default")
      (node (ref "K1") (pin "A3") (pinfunction "A3_A3") (pintype "passive"))
      (node (ref "K10") (pin "A3") (pinfunction "A3_A3") (pintype "passive"))
      (node (ref "K11") (pin "A3") (pinfunction "A3_A3") (pintype "passive"))
      (node (ref "K12") (pin "A3") (pinfunction "A3_A3") (pintype "passive"))
      (node (ref "K13") (pin "A3") (pinfunction "A3_A3") (pintype "passive"))
      (node (ref "K14") (pin "A3") (pinfunction "A3_A3") (pintype "passive"))
      (node (ref "K15") (pin "A3") (pinfunction "A3_A3") (pintype "passive"))
      (node (ref "K16") (pin "A3") (pinfunction "A3_A3") (pintype "passive"))
      (node (ref "K17") (pin "A3") (pinfunction "A3_A3") (pintype "passive"))
      (node (ref "K18") (pin "A3") (pinfunction "A3_A3") (pintype "passive"))
      (node (ref "K19") (pin "A3") (pinfunction "A3_A3") (pintype "passive"))
      (node (ref "K20") (pin "A3") (pinfunction "A3_A3") (pintype "passive"))
      (node (ref "K21") (pin "A3") (pinfunction "A3_A3") (pintype "passive"))
      (node (ref "K22") (pin "A3") (pinfunction "A3_A3") (pintype "passive"))
      (node (ref "K23") (pin "A3") (pinfunction "A3_A3") (pintype "passive"))
      (node (ref "K24") (pin "A3") (pinfunction "A3_A3") (pintype "passive"))
      (node (ref "K25") (pin "A3") (pinfunction "A3_A3") (pintype "passive"))
      (node (ref "K26") (pin "A3") (pinfunction "A3_A3") (pintype "passive"))
      (node (ref "K4") (pin "A3") (pinfunction "A3_A3") (pintype "passive"))
      (node (ref "K5") (pin "A3") (pinfunction "A3_A3") (pintype "passive"))
      (node (ref "K6") (pin "A3") (pinfunction "A3_A3") (pintype "passive"))
      (node (ref "K7") (pin "A3") (pinfunction "A3_A3") (pintype "passive"))
      (node (ref "K8") (pin "A3") (pinfunction "A3_A3") (pintype "passive"))
      (node (ref "K9") (pin "A3") (pinfunction "A3_A3") (pintype "passive"))
    )
    (net (code "2") (name "/R1_A1") (class "Default")
      (node (ref "R34") (pin "2") (pinfunction "2_2") (pintype "passive"))
    )
    (net (code "3") (name "/R1_A2") (class "Default")
      (node (ref "R33") (pin "2") (pinfunction "2_2") (pintype "passive"))
    )
    (net (code "4") (name "/R1_COM") (class "Default")
      (node (ref "K1") (pin "11") (pinfunction "11_11") (pintype "passive"))
    )
    (net (code "5") (name "/R1_NC") (class "Default")
      (node (ref "K1") (pin "12") (pinfunction "12_12") (pintype "passive"))
    )
    (net (code "6") (name "/R1_NO") (class "Default")
      (node (ref "K1") (pin "14") (pinfunction "14_14") (pintype "passive"))
    )
    (net (code "7") (name "/R2_A1") (class "Default")
      (node (ref "R57") (pin "2") (pinfunction "2_2") (pintype "passive"))
    )
    (net (code "8") (name "/R2_A2") (class "Default")
      (node (ref "R56") (pin "2") (pinfunction "2_2") (pintype "passive"))
    )
    (net (code "9") (name "/R2_COM") (class "Default")
      (node (ref "K4") (pin "11") (pinfunction "11_11") (pintype "passive"))
    )
    (net (code "10") (name "/R2_NC") (class "Default")
      (node (ref "K4") (pin "12") (pinfunction "12_12") (pintype "passive"))
    )
    (net (code "11") (name "/R2_NO") (class "Default")
      (node (ref "K4") (pin "14") (pinfunction "14_14") (pintype "passive"))
    )
    (net (code "12") (name "/R3_A1") (class "Default")
      (node (ref "R61") (pin "2") (pinfunction "2_2") (pintype "passive"))
    )
    (net (code "13") (name "/R3_A2") (class "Default")
      (node (ref "R60") (pin "2") (pinfunction "2_2") (pintype "passive"))
    )
    (net (code "14") (name "/R3_COM") (class "Default")
      (node (ref "K5") (pin "11") (pinfunction "11_11") (pintype "passive"))
    )
    (net (code "15") (name "/R3_NC") (class "Default")
      (node (ref "K5") (pin "12") (pinfunction "12_12") (pintype "passive"))
    )
    (net (code "16") (name "/R3_NO") (class "Default")
      (node (ref "K5") (pin "14") (pinfunction "14_14") (pintype "passive"))
    )
    (net (code "17") (name "/R4_A1") (class "Default")
      (node (ref "R65") (pin "2") (pinfunction "2_2") (pintype "passive"))
    )
    (net (code "18") (name "/R4_A2") (class "Default")
      (node (ref "R64") (pin "2") (pinfunction "2_2") (pintype "passive"))
    )
    (net (code "19") (name "/R4_COM") (class "Default")
      (node (ref "K6") (pin "11") (pinfunction "11_11") (pintype "passive"))
    )
    (net (code "20") (name "/R4_NC") (class "Default")
      (node (ref "K6") (pin "12") (pinfunction "12_12") (pintype "passive"))
    )
    (net (code "21") (name "/R4_NO") (class "Default")
      (node (ref "K6") (pin "14") (pinfunction "14_14") (pintype "passive"))
    )
    (net (code "22") (name "/R5_A1") (class "Default")
      (node (ref "R69") (pin "2") (pinfunction "2_2") (pintype "passive"))
    )
    (net (code "23") (name "/R5_A2") (class "Default")
      (node (ref "R68") (pin "2") (pinfunction "2_2") (pintype "passive"))
    )
    (net (code "24") (name "/R5_COM") (class "Default")
      (node (ref "K7") (pin "11") (pinfunction "11_11") (pintype "passive"))
    )
    (net (code "25") (name "/R5_NC") (class "Default")
      (node (ref "K7") (pin "12") (pinfunction "12_12") (pintype "passive"))
    )
    (net (code "26") (name "/R5_NO") (class "Default")
      (node (ref "K7") (pin "14") (pinfunction "14_14") (pintype "passive"))
    )
    (net (code "27") (name "/R6_A1") (class "Default")
      (node (ref "R73") (pin "2") (pinfunction "2_2") (pintype "passive"))
    )
    (net (code "28") (name "/R6_A2") (class "Default")
      (node (ref "R72") (pin "2") (pinfunction "2_2") (pintype "passive"))
    )
    (net (code "29") (name "/R6_COM") (class "Default")
      (node (ref "K8") (pin "11") (pinfunction "11_11") (pintype "passive"))
    )
    (net (code "30") (name "/R6_NC") (class "Default")
      (node (ref "K8") (pin "12") (pinfunction "12_12") (pintype "passive"))
    )
    (net (code "31") (name "/R6_NO") (class "Default")
      (node (ref "K8") (pin "14") (pinfunction "14_14") (pintype "passive"))
    )
    (net (code "32") (name "/R7_A1") (class "Default")
      (node (ref "R77") (pin "2") (pinfunction "2_2") (pintype "passive"))
    )
    (net (code "33") (name "/R7_A2") (class "Default")
      (node (ref "R76") (pin "2") (pinfunction "2_2") (pintype "passive"))
    )
    (net (code "34") (name "/R7_COM") (class "Default")
      (node (ref "K9") (pin "11") (pinfunction "11_11") (pintype "passive"))
    )
    (net (code "35") (name "/R7_NC") (class "Default")
      (node (ref "K9") (pin "12") (pinfunction "12_12") (pintype "passive"))
    )
    (net (code "36") (name "/R7_NO") (class "Default")
      (node (ref "K9") (pin "14") (pinfunction "14_14") (pintype "passive"))
    )
    (net (code "37") (name "/R8_A1") (class "Default")
      (node (ref "R81") (pin "2") (pinfunction "2_2") (pintype "passive"))
    )
    (net (code "38") (name "/R8_A2") (class "Default")
      (node (ref "R80") (pin "2") (pinfunction "2_2") (pintype "passive"))
    )
    (net (code "39") (name "/R8_COM") (class "Default")
      (node (ref "K10") (pin "11") (pinfunction "11_11") (pintype "passive"))
    )
    (net (code "40") (name "/R8_NC") (class "Default")
      (node (ref "K10") (pin "12") (pinfunction "12_12") (pintype "passive"))
    )
    (net (code "41") (name "/R8_NO") (class "Default")
      (node (ref "K10") (pin "14") (pinfunction "14_14") (pintype "passive"))
    )
    (net (code "42") (name "/R9_A1") (class "Default")
      (node (ref "R93") (pin "2") (pinfunction "2_2") (pintype "passive"))
    )
    (net (code "43") (name "/R9_A2") (class "Default")
      (node (ref "R91") (pin "2") (pinfunction "2_2") (pintype "passive"))
    )
    (net (code "44") (name "/R9_COM") (class "Default")
      (node (ref "K11") (pin "11") (pinfunction "11_11") (pintype "passive"))
    )
    (net (code "45") (name "/R9_NC") (class "Default")
      (node (ref "K11") (pin "12") (pinfunction "12_12") (pintype "passive"))
    )
    (net (code "46") (name "/R9_NO") (class "Default")
      (node (ref "K11") (pin "14") (pinfunction "14_14") (pintype "passive"))
    )
    (net (code "47") (name "/R10_A1") (class "Default")
      (node (ref "R94") (pin "2") (pinfunction "2_2") (pintype "passive"))
    )
    (net (code "48") (name "/R10_A2") (class "Default")
      (node (ref "R92") (pin "2") (pinfunction "2_2") (pintype "passive"))
    )
    (net (code "49") (name "/R10_COM") (class "Default")
      (node (ref "K12") (pin "11") (pinfunction "11_11") (pintype "passive"))
    )
    (net (code "50") (name "/R10_NC") (class "Default")
      (node (ref "K12") (pin "12") (pinfunction "12_12") (pintype "passive"))
    )
    (net (code "51") (name "/R10_NO") (class "Default")
      (node (ref "K12") (pin "14") (pinfunction "14_14") (pintype "passive"))
    )
    (net (code "52") (name "/R11_A1") (class "Default")
      (node (ref "R100") (pin "2") (pinfunction "2_2") (pintype "passive"))
    )
    (net (code "53") (name "/R11_A2") (class "Default")
      (node (ref "R99") (pin "2") (pinfunction "2_2") (pintype "passive"))
    )
    (net (code "54") (name "/R11_COM") (class "Default")
      (node (ref "K13") (pin "11") (pinfunction "11_11") (pintype "passive"))
    )
    (net (code "55") (name "/R11_NC") (class "Default")
      (node (ref "K13") (pin "12") (pinfunction "12_12") (pintype "passive"))
    )
    (net (code "56") (name "/R11_NO") (class "Default")
      (node (ref "K13") (pin "14") (pinfunction "14_14") (pintype "passive"))
    )
    (net (code "57") (name "/R12_A1") (class "Default")
      (node (ref "R104") (pin "2") (pinfunction "2_2") (pintype "passive"))
    )
    (net (code "58") (name "/R12_A2") (class "Default")
      (node (ref "R103") (pin "2") (pinfunction "2_2") (pintype "passive"))
    )
    (net (code "59") (name "/R12_COM") (class "Default")
      (node (ref "K14") (pin "11") (pinfunction "11_11") (pintype "passive"))
    )
    (net (code "60") (name "/R12_NC") (class "Default")
      (node (ref "K14") (pin "12") (pinfunction "12_12") (pintype "passive"))
    )
    (net (code "61") (name "/R12_NO") (class "Default")
      (node (ref "K14") (pin "14") (pinfunction "14_14") (pintype "passive"))
    )
    (net (code "62") (name "/R13_A1") (class "Default")
      (node (ref "R108") (pin "2") (pinfunction "2_2") (pintype "passive"))
    )
    (net (code "63") (name "/R13_A2") (class "Default")
      (node (ref "R107") (pin "2") (pinfunction "2_2") (pintype "passive"))
    )
    (net (code "64") (name "/R13_COM") (class "Default")
      (node (ref "K15") (pin "11") (pinfunction "11_11") (pintype "passive"))
    )
    (net (code "65") (name "/R13_NC") (class "Default")
      (node (ref "K15") (pin "12") (pinfunction "12_12") (pintype "passive"))
    )
    (net (code "66") (name "/R13_NO") (class "Default")
      (node (ref "K15") (pin "14") (pinfunction "14_14") (pintype "passive"))
    )
    (net (code "67") (name "/R14_A1") (class "Default")
      (node (ref "R112") (pin "2") (pinfunction "2_2") (pintype "passive"))
    )
    (net (code "68") (name "/R14_A2") (class "Default")
      (node (ref "R111") (pin "2") (pinfunction "2_2") (pintype "passive"))
    )
    (net (code "69") (name "/R14_COM") (class "Default")
      (node (ref "K16") (pin "11") (pinfunction "11_11") (pintype "passive"))
    )
    (net (code "70") (name "/R14_NC") (class "Default")
      (node (ref "K16") (pin "12") (pinfunction "12_12") (pintype "passive"))
    )
    (net (code "71") (name "/R14_NO") (class "Default")
      (node (ref "K16") (pin "14") (pinfunction "14_14") (pintype "passive"))
    )
    (net (code "72") (name "/R15_A1") (class "Default")
      (node (ref "R116") (pin "2") (pinfunction "2_2") (pintype "passive"))
    )
    (net (code "73") (name "/R15_A2") (class "Default")
      (node (ref "R115") (pin "2") (pinfunction "2_2") (pintype "passive"))
    )
    (net (code "74") (name "/R15_COM") (class "Default")
      (node (ref "K17") (pin "11") (pinfunction "11_11") (pintype "passive"))
    )
    (net (code "75") (name "/R15_NC") (class "Default")
      (node (ref "K17") (pin "12") (pinfunction "12_12") (pintype "passive"))
    )
    (net (code "76") (name "/R15_NO") (class "Default")
      (node (ref "K17") (pin "14") (pinfunction "14_14") (pintype "passive"))
    )
    (net (code "77") (name "/R16_A1") (class "Default")
      (node (ref "R120") (pin "2") (pinfunction "2_2") (pintype "passive"))
    )
    (net (code "78") (name "/R16_A2") (class "Default")
      (node (ref "R119") (pin "2") (pinfunction "2_2") (pintype "passive"))
    )
    (net (code "79") (name "/R16_COM") (class "Default")
      (node (ref "K18") (pin "11") (pinfunction "11_11") (pintype "passive"))
    )
    (net (code "80") (name "/R16_NC") (class "Default")
      (node (ref "K18") (pin "12") (pinfunction "12_12") (pintype "passive"))
    )
    (net (code "81") (name "/R16_NO") (class "Default")
      (node (ref "K18") (pin "14") (pinfunction "14_14") (pintype "passive"))
    )
    (net (code "82") (name "/R17_A1") (class "Default")
      (node (ref "R124") (pin "2") (pinfunction "2_2") (pintype "passive"))
    )
    (net (code "83") (name "/R17_A2") (class "Default")
      (node (ref "R123") (pin "2") (pinfunction "2_2") (pintype "passive"))
    )
    (net (code "84") (name "/R17_COM") (class "Default")
      (node (ref "K19") (pin "11") (pinfunction "11_11") (pintype "passive"))
    )
    (net (code "85") (name "/R17_NC") (class "Default")
      (node (ref "K19") (pin "12") (pinfunction "12_12") (pintype "passive"))
    )
    (net (code "86") (name "/R17_NO") (class "Default")
      (node (ref "K19") (pin "14") (pinfunction "14_14") (pintype "passive"))
    )
    (net (code "87") (name "/R18_A1") (class "Default")
      (node (ref "R128") (pin "2") (pinfunction "2_2") (pintype "passive"))
    )
    (net (code "88") (name "/R18_A2") (class "Default")
      (node (ref "R127") (pin "2") (pinfunction "2_2") (pintype "passive"))
    )
    (net (code "89") (name "/R18_COM") (class "Default")
      (node (ref "K20") (pin "11") (pinfunction "11_11") (pintype "passive"))
    )
    (net (code "90") (name "/R18_NC") (class "Default")
      (node (ref "K20") (pin "12") (pinfunction "12_12") (pintype "passive"))
    )
    (net (code "91") (name "/R18_NO") (class "Default")
      (node (ref "K20") (pin "14") (pinfunction "14_14") (pintype "passive"))
    )
    (net (code "92") (name "/R19_A1") (class "Default")
      (node (ref "R132") (pin "2") (pinfunction "2_2") (pintype "passive"))
    )
    (net (code "93") (name "/R19_A2") (class "Default")
      (node (ref "R131") (pin "2") (pinfunction "2_2") (pintype "passive"))
    )
    (net (code "94") (name "/R19_COM") (class "Default")
      (node (ref "K21") (pin "11") (pinfunction "11_11") (pintype "passive"))
    )
    (net (code "95") (name "/R19_NC") (class "Default")
      (node (ref "K21") (pin "12") (pinfunction "12_12") (pintype "passive"))
    )
    (net (code "96") (name "/R19_NO") (class "Default")
      (node (ref "K21") (pin "14") (pinfunction "14_14") (pintype "passive"))
    )
    (net (code "97") (name "/R20_A1") (class "Default")
      (node (ref "R136") (pin "2") (pinfunction "2_2") (pintype "passive"))
    )
    (net (code "98") (name "/R20_A2") (class "Default")
      (node (ref "R135") (pin "2") (pinfunction "2_2") (pintype "passive"))
    )
    (net (code "99") (name "/R20_COM") (class "Default")
      (node (ref "K22") (pin "11") (pinfunction "11_11") (pintype "passive"))
    )
    (net (code "100") (name "/R20_NC") (class "Default")
      (node (ref "K22") (pin "12") (pinfunction "12_12") (pintype "passive"))
    )
    (net (code "101") (name "/R20_NO") (class "Default")
      (node (ref "K22") (pin "14") (pinfunction "14_14") (pintype "passive"))
    )
    (net (code "102") (name "/R21_A1") (class "Default")
      (node (ref "R140") (pin "2") (pinfunction "2_2") (pintype "passive"))
    )
    (net (code "103") (name "/R21_A2") (class "Default")
      (node (ref "R139") (pin "2") (pinfunction "2_2") (pintype "passive"))
    )
    (net (code "104") (name "/R21_COM") (class "Default")
      (node (ref "K23") (pin "11") (pinfunction "11_11") (pintype "passive"))
    )
    (net (code "105") (name "/R21_NC") (class "Default")
      (node (ref "K23") (pin "12") (pinfunction "12_12") (pintype "passive"))
    )
    (net (code "106") (name "/R21_NO") (class "Default")
      (node (ref "K23") (pin "14") (pinfunction "14_14") (pintype "passive"))
    )
    (net (code "107") (name "/R22_A1") (class "Default")
      (node (ref "R144") (pin "2") (pinfunction "2_2") (pintype "passive"))
    )
    (net (code "108") (name "/R22_A2") (class "Default")
      (node (ref "R143") (pin "2") (pinfunction "2_2") (pintype "passive"))
    )
    (net (code "109") (name "/R22_COM") (class "Default")
      (node (ref "K24") (pin "11") (pinfunction "11_11") (pintype "passive"))
    )
    (net (code "110") (name "/R22_NC") (class "Default")
      (node (ref "K24") (pin "12") (pinfunction "12_12") (pintype "passive"))
    )
    (net (code "111") (name "/R22_NO") (class "Default")
      (node (ref "K24") (pin "14") (pinfunction "14_14") (pintype "passive"))
    )
    (net (code "112") (name "/R23_A1") (class "Default")
      (node (ref "R148") (pin "2") (pinfunction "2_2") (pintype "passive"))
    )
    (net (code "113") (name "/R23_A2") (class "Default")
      (node (ref "R147") (pin "2") (pinfunction "2_2") (pintype "passive"))
    )
    (net (code "114") (name "/R23_COM") (class "Default")
      (node (ref "K25") (pin "11") (pinfunction "11_11") (pintype "passive"))
    )
    (net (code "115") (name "/R23_NC") (class "Default")
      (node (ref "K25") (pin "12") (pinfunction "12_12") (pintype "passive"))
    )
    (net (code "116") (name "/R23_NO") (class "Default")
      (node (ref "K25") (pin "14") (pinfunction "14_14") (pintype "passive"))
    )
    (net (code "117") (name "/R24_A1") (class "Default")
      (node (ref "R152") (pin "2") (pinfunction "2_2") (pintype "passive"))
    )
    (net (code "118") (name "/R24_A2") (class "Default")
      (node (ref "R151") (pin "2") (pinfunction "2_2") (pintype "passive"))
    )
    (net (code "119") (name "/R24_COM") (class "Default")
      (node (ref "K26") (pin "11") (pinfunction "11_11") (pintype "passive"))
    )
    (net (code "120") (name "/R24_NC") (class "Default")
      (node (ref "K26") (pin "12") (pinfunction "12_12") (pintype "passive"))
    )
    (net (code "121") (name "/R24_NO") (class "Default")
      (node (ref "K26") (pin "14") (pinfunction "14_14") (pintype "passive"))
    )
    (net (code "122") (name "GND") (class "Default")
      (node (ref "C12") (pin "1") (pinfunction "1_1") (pintype "passive"))
      (node (ref "C13") (pin "1") (pinfunction "1_1") (pintype "passive"))
      (node (ref "C14") (pin "1") (pinfunction "1_1") (pintype "passive"))
      (node (ref "C15") (pin "1") (pinfunction "1_1") (pintype "passive"))
      (node (ref "C16") (pin "1") (pinfunction "1_1") (pintype "passive"))
      (node (ref "C17") (pin "1") (pinfunction "1_1") (pintype "passive"))
      (node (ref "C18") (pin "1") (pinfunction "1_1") (pintype "passive"))
      (node (ref "C19") (pin "1") (pinfunction "1_1") (pintype "passive"))
      (node (ref "C20") (pin "1") (pinfunction "1_1") (pintype "passive"))
      (node (ref "C21") (pin "1") (pinfunction "1_1") (pintype "passive"))
      (node (ref "C22") (pin "1") (pinfunction "1_1") (pintype "passive"))
      (node (ref "C23") (pin "1") (pinfunction "1_1") (pintype "passive"))
      (node (ref "C24") (pin "1") (pinfunction "1_1") (pintype "passive"))
      (node (ref "C25") (pin "1") (pinfunction "1_1") (pintype "passive"))
      (node (ref "C26") (pin "1") (pinfunction "1_1") (pintype "passive"))
      (node (ref "C27") (pin "1") (pinfunction "1_1") (pintype "passive"))
      (node (ref "C28") (pin "1") (pinfunction "1_1") (pintype "passive"))
      (node (ref "C29") (pin "1") (pinfunction "1_1") (pintype "passive"))
      (node (ref "C30") (pin "1") (pinfunction "1_1") (pintype "passive"))
      (node (ref "C31") (pin "1") (pinfunction "1_1") (pintype "passive"))
      (node (ref "C32") (pin "1") (pinfunction "1_1") (pintype "passive"))
      (node (ref "C37") (pin "1") (pinfunction "1_1") (pintype "passive"))
      (node (ref "C38") (pin "1") (pinfunction "1_1") (pintype "passive"))
      (node (ref "C39") (pin "1") (pinfunction "1_1") (pintype "passive"))
      (node (ref "C40") (pin "1") (pinfunction "1_1") (pintype "passive"))
      (node (ref "C41") (pin "1") (pinfunction "1_1") (pintype "passive"))
      (node (ref "C42") (pin "1") (pinfunction "1_1") (pintype "passive"))
      (node (ref "C43") (pin "1") (pinfunction "1_1") (pintype "passive"))
      (node (ref "C44") (pin "1") (pinfunction "1_1") (pintype "passive"))
      (node (ref "C45") (pin "1") (pinfunction "1_1") (pintype "passive"))
      (node (ref "C46") (pin "1") (pinfunction "1_1") (pintype "passive"))
      (node (ref "C47") (pin "1") (pinfunction "1_1") (pintype "passive"))
      (node (ref "C48") (pin "1") (pinfunction "1_1") (pintype "passive"))
      (node (ref "C49") (pin "1") (pinfunction "1_1") (pintype "passive"))
      (node (ref "C50") (pin "1") (pinfunction "1_1") (pintype "passive"))
      (node (ref "C51") (pin "1") (pinfunction "1_1") (pintype "passive"))
      (node (ref "C52") (pin "1") (pinfunction "1_1") (pintype "passive"))
      (node (ref "C53") (pin "1") (pinfunction "1_1") (pintype "passive"))
      (node (ref "C54") (pin "1") (pinfunction "1_1") (pintype "passive"))
      (node (ref "C55") (pin "1") (pinfunction "1_1") (pintype "passive"))
      (node (ref "C56") (pin "1") (pinfunction "1_1") (pintype "passive"))
      (node (ref "C57") (pin "1") (pinfunction "1_1") (pintype "passive"))
      (node (ref "C58") (pin "1") (pinfunction "1_1") (pintype "passive"))
      (node (ref "C59") (pin "1") (pinfunction "1_1") (pintype "passive"))
      (node (ref "C6") (pin "1") (pinfunction "1_1") (pintype "passive"))
      (node (ref "C60") (pin "1") (pinfunction "1_1") (pintype "passive"))
      (node (ref "C61") (pin "1") (pinfunction "1_1") (pintype "passive"))
      (node (ref "C7") (pin "1") (pinfunction "1_1") (pintype "passive"))
      (node (ref "Q18") (pin "2") (pinfunction "S_2") (pintype "passive"))
      (node (ref "Q19") (pin "2") (pinfunction "S_2") (pintype "passive"))
      (node (ref "Q20") (pin "2") (pinfunction "S_2") (pintype "passive"))
      (node (ref "Q21") (pin "2") (pinfunction "S_2") (pintype "passive"))
      (node (ref "Q22") (pin "2") (pinfunction "S_2") (pintype "passive"))
      (node (ref "Q23") (pin "2") (pinfunction "S_2") (pintype "passive"))
      (node (ref "Q24") (pin "2") (pinfunction "S_2") (pintype "passive"))
      (node (ref "Q25") (pin "2") (pinfunction "S_2") (pintype "passive"))
      (node (ref "Q26") (pin "2") (pinfunction "S_2") (pintype "passive"))
      (node (ref "Q27") (pin "2") (pinfunction "S_2") (pintype "passive"))
      (node (ref "Q28") (pin "2") (pinfunction "S_2") (pintype "passive"))
      (node (ref "Q29") (pin "2") (pinfunction "S_2") (pintype "passive"))
      (node (ref "Q3") (pin "2") (pinfunction "S_2") (pintype "passive"))
      (node (ref "Q30") (pin "2") (pinfunction "S_2") (pintype "passive"))
      (node (ref "Q31") (pin "2") (pinfunction "S_2") (pintype "passive"))
      (node (ref "Q33") (pin "2") (pinfunction "S_2") (pintype "passive"))
      (node (ref "Q34") (pin "2") (pinfunction "S_2") (pintype "passive"))
      (node (ref "Q35") (pin "2") (pinfunction "S_2") (pintype "passive"))
      (node (ref "Q36") (pin "2") (pinfunction "S_2") (pintype "passive"))
      (node (ref "Q37") (pin "2") (pinfunction "S_2") (pintype "passive"))
      (node (ref "Q38") (pin "2") (pinfunction "S_2") (pintype "passive"))
      (node (ref "Q39") (pin "2") (pinfunction "S_2") (pintype "passive"))
      (node (ref "Q4") (pin "2") (pinfunction "S_2") (pintype "passive"))
      (node (ref "Q40") (pin "2") (pinfunction "S_2") (pintype "passive"))
      (node (ref "Q41") (pin "2") (pinfunction "S_2") (pintype "passive"))
      (node (ref "Q42") (pin "2") (pinfunction "S_2") (pintype "passive"))
      (node (ref "Q43") (pin "2") (pinfunction "S_2") (pintype "passive"))
      (node (ref "Q44") (pin "2") (pinfunction "S_2") (pintype "passive"))
      (node (ref "Q45") (pin "2") (pinfunction "S_2") (pintype "passive"))
      (node (ref "Q46") (pin "2") (pinfunction "S_2") (pintype "passive"))
      (node (ref "Q47") (pin "2") (pinfunction "S_2") (pintype "passive"))
      (node (ref "Q48") (pin "2") (pinfunction "S_2") (pintype "passive"))
      (node (ref "Q49") (pin "2") (pinfunction "S_2") (pintype "passive"))
      (node (ref "Q50") (pin "2") (pinfunction "S_2") (pintype "passive"))
      (node (ref "Q51") (pin "2") (pinfunction "S_2") (pintype "passive"))
      (node (ref "Q52") (pin "2") (pinfunction "S_2") (pintype "passive"))
      (node (ref "Q53") (pin "2") (pinfunction "S_2") (pintype "passive"))
      (node (ref "Q54") (pin "2") (pinfunction "S_2") (pintype "passive"))
      (node (ref "Q55") (pin "2") (pinfunction "S_2") (pintype "passive"))
      (node (ref "Q56") (pin "2") (pinfunction "S_2") (pintype "passive"))
      (node (ref "Q57") (pin "2") (pinfunction "S_2") (pintype "passive"))
      (node (ref "Q58") (pin "2") (pinfunction "S_2") (pintype "passive"))
      (node (ref "Q59") (pin "2") (pinfunction "S_2") (pintype "passive"))
      (node (ref "Q60") (pin "2") (pinfunction "S_2") (pintype "passive"))
      (node (ref "Q61") (pin "2") (pinfunction "S_2") (pintype "passive"))
      (node (ref "Q62") (pin "2") (pinfunction "S_2") (pintype "passive"))
      (node (ref "Q63") (pin "2") (pinfunction "S_2") (pintype "passive"))
      (node (ref "Q64") (pin "2") (pinfunction "S_2") (pintype "passive"))
      (node (ref "R101") (pin "1") (pinfunction "1_1") (pintype "passive"))
      (node (ref "R102") (pin "1") (pinfunction "1_1") (pintype "passive"))
      (node (ref "R105") (pin "1") (pinfunction "1_1") (pintype "passive"))
      (node (ref "R106") (pin "1") (pinfunction "1_1") (pintype "passive"))
      (node (ref "R109") (pin "1") (pinfunction "1_1") (pintype "passive"))
      (node (ref "R110") (pin "1") (pinfunction "1_1") (pintype "passive"))
      (node (ref "R113") (pin "1") (pinfunction "1_1") (pintype "passive"))
      (node (ref "R114") (pin "1") (pinfunction "1_1") (pintype "passive"))
      (node (ref "R117") (pin "1") (pinfunction "1_1") (pintype "passive"))
      (node (ref "R118") (pin "1") (pinfunction "1_1") (pintype "passive"))
      (node (ref "R121") (pin "1") (pinfunction "1_1") (pintype "passive"))
      (node (ref "R122") (pin "1") (pinfunction "1_1") (pintype "passive"))
      (node (ref "R125") (pin "1") (pinfunction "1_1") (pintype "passive"))
      (node (ref "R126") (pin "1") (pinfunction "1_1") (pintype "passive"))
      (node (ref "R129") (pin "1") (pinfunction "1_1") (pintype "passive"))
      (node (ref "R130") (pin "1") (pinfunction "1_1") (pintype "passive"))
      (node (ref "R133") (pin "1") (pinfunction "1_1") (pintype "passive"))
      (node (ref "R134") (pin "1") (pinfunction "1_1") (pintype "passive"))
      (node (ref "R137") (pin "1") (pinfunction "1_1") (pintype "passive"))
      (node (ref "R138") (pin "1") (pinfunction "1_1") (pintype "passive"))
      (node (ref "R141") (pin "1") (pinfunction "1_1") (pintype "passive"))
      (node (ref "R142") (pin "1") (pinfunction "1_1") (pintype "passive"))
      (node (ref "R145") (pin "1") (pinfunction "1_1") (pintype "passive"))
      (node (ref "R146") (pin "1") (pinfunction "1_1") (pintype "passive"))
      (node (ref "R149") (pin "1") (pinfunction "1_1") (pintype "passive"))
      (node (ref "R150") (pin "1") (pinfunction "1_1") (pintype "passive"))
      (node (ref "R153") (pin "1") (pinfunction "1_1") (pintype "passive"))
      (node (ref "R154") (pin "1") (pinfunction "1_1") (pintype "passive"))
      (node (ref "R32") (pin "1") (pinfunction "1_1") (pintype "passive"))
      (node (ref "R35") (pin "1") (pinfunction "1_1") (pintype "passive"))
      (node (ref "R58") (pin "1") (pinfunction "1_1") (pintype "passive"))
      (node (ref "R59") (pin "1") (pinfunction "1_1") (pintype "passive"))
      (node (ref "R62") (pin "1") (pinfunction "1_1") (pintype "passive"))
      (node (ref "R63") (pin "1") (pinfunction "1_1") (pintype "passive"))
      (node (ref "R66") (pin "1") (pinfunction "1_1") (pintype "passive"))
      (node (ref "R67") (pin "1") (pinfunction "1_1") (pintype "passive"))
      (node (ref "R70") (pin "1") (pinfunction "1_1") (pintype "passive"))
      (node (ref "R71") (pin "1") (pinfunction "1_1") (pintype "passive"))
      (node (ref "R74") (pin "1") (pinfunction "1_1") (pintype "passive"))
      (node (ref "R75") (pin "1") (pinfunction "1_1") (pintype "passive"))
      (node (ref "R78") (pin "1") (pinfunction "1_1") (pintype "passive"))
      (node (ref "R79") (pin "1") (pinfunction "1_1") (pintype "passive"))
      (node (ref "R82") (pin "1") (pinfunction "1_1") (pintype "passive"))
      (node (ref "R83") (pin "1") (pinfunction "1_1") (pintype "passive"))
      (node (ref "R95") (pin "1") (pinfunction "1_1") (pintype "passive"))
      (node (ref "R96") (pin "1") (pinfunction "1_1") (pintype "passive"))
      (node (ref "R97") (pin "1") (pinfunction "1_1") (pintype "passive"))
      (node (ref "R98") (pin "1") (pinfunction "1_1") (pintype "passive"))
    )
    (net (code "123") (name "Net-(Q3-D)") (class "Default")
      (node (ref "K1") (pin "A2") (pinfunction "A2_A2") (pintype "passive"))
      (node (ref "Q3") (pin "3") (pinfunction "D_3") (pintype "passive"))
    )
    (net (code "124") (name "Net-(Q3-G)") (class "Default")
      (node (ref "C6") (pin "2") (pinfunction "2_2") (pintype "passive"))
      (node (ref "Q3") (pin "1") (pinfunction "G_1") (pintype "passive"))
      (node (ref "R32") (pin "2") (pinfunction "2_2") (pintype "passive"))
      (node (ref "R33") (pin "1") (pinfunction "1_1") (pintype "passive"))
    )
    (net (code "125") (name "Net-(Q4-D)") (class "Default")
      (node (ref "K1") (pin "A1") (pinfunction "A1_A1") (pintype "passive"))
      (node (ref "Q4") (pin "3") (pinfunction "D_3") (pintype "passive"))
    )
    (net (code "126") (name "Net-(Q4-G)") (class "Default")
      (node (ref "C7") (pin "2") (pinfunction "2_2") (pintype "passive"))
      (node (ref "Q4") (pin "1") (pinfunction "G_1") (pintype "passive"))
      (node (ref "R34") (pin "1") (pinfunction "1_1") (pintype "passive"))
      (node (ref "R35") (pin "2") (pinfunction "2_2") (pintype "passive"))
    )
    (net (code "127") (name "Net-(Q18-D)") (class "Default")
      (node (ref "K4") (pin "A1") (pinfunction "A1_A1") (pintype "passive"))
      (node (ref "Q18") (pin "3") (pinfunction "D_3") (pintype "passive"))
    )
    (net (code "128") (name "Net-(Q18-G)") (class "Default")
      (node (ref "C12") (pin "2") (pinfunction "2_2") (pintype "passive"))
      (node (ref "Q18") (pin "1") (pinfunction "G_1") (pintype "passive"))
      (node (ref "R57") (pin "1") (pinfunction "1_1") (pintype "passive"))
      (node (ref "R58") (pin "2") (pinfunction "2_2") (pintype "passive"))
    )
    (net (code "129") (name "Net-(Q19-D)") (class "Default")
      (node (ref "K4") (pin "A2") (pinfunction "A2_A2") (pintype "passive"))
      (node (ref "Q19") (pin "3") (pinfunction "D_3") (pintype "passive"))
    )
    (net (code "130") (name "Net-(Q19-G)") (class "Default")
      (node (ref "C13") (pin "2") (pinfunction "2_2") (pintype "passive"))
      (node (ref "Q19") (pin "1") (pinfunction "G_1") (pintype "passive"))
      (node (ref "R56") (pin "1") (pinfunction "1_1") (pintype "passive"))
      (node (ref "R59") (pin "2") (pinfunction "2_2") (pintype "passive"))
    )
    (net (code "131") (name "Net-(Q20-D)") (class "Default")
      (node (ref "K5") (pin "A1") (pinfunction "A1_A1") (pintype "passive"))
      (node (ref "Q20") (pin "3") (pinfunction "D_3") (pintype "passive"))
    )
    (net (code "132") (name "Net-(Q20-G)") (class "Default")
      (node (ref "C14") (pin "2") (pinfunction "2_2") (pintype "passive"))
      (node (ref "Q20") (pin "1") (pinfunction "G_1") (pintype "passive"))
      (node (ref "R61") (pin "1") (pinfunction "1_1") (pintype "passive"))
      (node (ref "R62") (pin "2") (pinfunction "2_2") (pintype "passive"))
    )
    (net (code "133") (name "Net-(Q21-D)") (class "Default")
      (node (ref "K5") (pin "A2") (pinfunction "A2_A2") (pintype "passive"))
      (node (ref "Q21") (pin "3") (pinfunction "D_3") (pintype "passive"))
    )
    (net (code "134") (name "Net-(Q21-G)") (class "Default")
      (node (ref "C15") (pin "2") (pinfunction "2_2") (pintype "passive"))
      (node (ref "Q21") (pin "1") (pinfunction "G_1") (pintype "passive"))
      (node (ref "R60") (pin "1") (pinfunction "1_1") (pintype "passive"))
      (node (ref "R63") (pin "2") (pinfunction "2_2") (pintype "passive"))
    )
    (net (code "135") (name "Net-(Q22-D)") (class "Default")
      (node (ref "K6") (pin "A1") (pinfunction "A1_A1") (pintype "passive"))
      (node (ref "Q22") (pin "3") (pinfunction "D_3") (pintype "passive"))
    )
    (net (code "136") (name "Net-(Q22-G)") (class "Default")
      (node (ref "C16") (pin "2") (pinfunction "2_2") (pintype "passive"))
      (node (ref "Q22") (pin "1") (pinfunction "G_1") (pintype "passive"))
      (node (ref "R65") (pin "1") (pinfunction "1_1") (pintype "passive"))
      (node (ref "R66") (pin "2") (pinfunction "2_2") (pintype "passive"))
    )
    (net (code "137") (name "Net-(Q23-D)") (class "Default")
      (node (ref "K6") (pin "A2") (pinfunction "A2_A2") (pintype "passive"))
      (node (ref "Q23") (pin "3") (pinfunction "D_3") (pintype "passive"))
    )
    (net (code "138") (name "Net-(Q23-G)") (class "Default")
      (node (ref "C17") (pin "2") (pinfunction "2_2") (pintype "passive"))
      (node (ref "Q23") (pin "1") (pinfunction "G_1") (pintype "passive"))
      (node (ref "R64") (pin "1") (pinfunction "1_1") (pintype "passive"))
      (node (ref "R67") (pin "2") (pinfunction "2_2") (pintype "passive"))
    )
    (net (code "139") (name "Net-(Q24-D)") (class "Default")
      (node (ref "K7") (pin "A1") (pinfunction "A1_A1") (pintype "passive"))
      (node (ref "Q24") (pin "3") (pinfunction "D_3") (pintype "passive"))
    )
    (net (code "140") (name "Net-(Q24-G)") (class "Default")
      (node (ref "C18") (pin "2") (pinfunction "2_2") (pintype "passive"))
      (node (ref "Q24") (pin "1") (pinfunction "G_1") (pintype "passive"))
      (node (ref "R69") (pin "1") (pinfunction "1_1") (pintype "passive"))
      (node (ref "R70") (pin "2") (pinfunction "2_2") (pintype "passive"))
    )
    (net (code "141") (name "Net-(Q25-D)") (class "Default")
      (node (ref "K7") (pin "A2") (pinfunction "A2_A2") (pintype "passive"))
      (node (ref "Q25") (pin "3") (pinfunction "D_3") (pintype "passive"))
    )
    (net (code "142") (name "Net-(Q25-G)") (class "Default")
      (node (ref "C19") (pin "2") (pinfunction "2_2") (pintype "passive"))
      (node (ref "Q25") (pin "1") (pinfunction "G_1") (pintype "passive"))
      (node (ref "R68") (pin "1") (pinfunction "1_1") (pintype "passive"))
      (node (ref "R71") (pin "2") (pinfunction "2_2") (pintype "passive"))
    )
    (net (code "143") (name "Net-(Q26-D)") (class "Default")
      (node (ref "K8") (pin "A1") (pinfunction "A1_A1") (pintype "passive"))
      (node (ref "Q26") (pin "3") (pinfunction "D_3") (pintype "passive"))
    )
    (net (code "144") (name "Net-(Q26-G)") (class "Default")
      (node (ref "C20") (pin "2") (pinfunction "2_2") (pintype "passive"))
      (node (ref "Q26") (pin "1") (pinfunction "G_1") (pintype "passive"))
      (node (ref "R73") (pin "1") (pinfunction "1_1") (pintype "passive"))
      (node (ref "R74") (pin "2") (pinfunction "2_2") (pintype "passive"))
    )
    (net (code "145") (name "Net-(Q27-D)") (class "Default")
      (node (ref "K8") (pin "A2") (pinfunction "A2_A2") (pintype "passive"))
      (node (ref "Q27") (pin "3") (pinfunction "D_3") (pintype "passive"))
    )
    (net (code "146") (name "Net-(Q27-G)") (class "Default")
      (node (ref "C21") (pin "2") (pinfunction "2_2") (pintype "passive"))
      (node (ref "Q27") (pin "1") (pinfunction "G_1") (pintype "passive"))
      (node (ref "R72") (pin "1") (pinfunction "1_1") (pintype "passive"))
      (node (ref "R75") (pin "2") (pinfunction "2_2") (pintype "passive"))
    )
    (net (code "147") (name "Net-(Q28-D)") (class "Default")
      (node (ref "K9") (pin "A1") (pinfunction "A1_A1") (pintype "passive"))
      (node (ref "Q28") (pin "3") (pinfunction "D_3") (pintype "passive"))
    )
    (net (code "148") (name "Net-(Q28-G)") (class "Default")
      (node (ref "C22") (pin "2") (pinfunction "2_2") (pintype "passive"))
      (node (ref "Q28") (pin "1") (pinfunction "G_1") (pintype "passive"))
      (node (ref "R77") (pin "1") (pinfunction "1_1") (pintype "passive"))
      (node (ref "R78") (pin "2") (pinfunction "2_2") (pintype "passive"))
    )
    (net (code "149") (name "Net-(Q29-D)") (class "Default")
      (node (ref "K9") (pin "A2") (pinfunction "A2_A2") (pintype "passive"))
      (node (ref "Q29") (pin "3") (pinfunction "D_3") (pintype "passive"))
    )
    (net (code "150") (name "Net-(Q29-G)") (class "Default")
      (node (ref "C23") (pin "2") (pinfunction "2_2") (pintype "passive"))
      (node (ref "Q29") (pin "1") (pinfunction "G_1") (pintype "passive"))
      (node (ref "R76") (pin "1") (pinfunction "1_1") (pintype "passive"))
      (node (ref "R79") (pin "2") (pinfunction "2_2") (pintype "passive"))
    )
    (net (code "151") (name "Net-(Q30-D)") (class "Default")
      (node (ref "K10") (pin "A1") (pinfunction "A1_A1") (pintype "passive"))
      (node (ref "Q30") (pin "3") (pinfunction "D_3") (pintype "passive"))
    )
    (net (code "152") (name "Net-(Q30-G)") (class "Default")
      (node (ref "C24") (pin "2") (pinfunction "2_2") (pintype "passive"))
      (node (ref "Q30") (pin "1") (pinfunction "G_1") (pintype "passive"))
      (node (ref "R81") (pin "1") (pinfunction "1_1") (pintype "passive"))
      (node (ref "R82") (pin "2") (pinfunction "2_2") (pintype "passive"))
    )
    (net (code "153") (name "Net-(Q31-D)") (class "Default")
      (node (ref "K10") (pin "A2") (pinfunction "A2_A2") (pintype "passive"))
      (node (ref "Q31") (pin "3") (pinfunction "D_3") (pintype "passive"))
    )
    (net (code "154") (name "Net-(Q31-G)") (class "Default")
      (node (ref "C25") (pin "2") (pinfunction "2_2") (pintype "passive"))
      (node (ref "Q31") (pin "1") (pinfunction "G_1") (pintype "passive"))
      (node (ref "R80") (pin "1") (pinfunction "1_1") (pintype "passive"))
      (node (ref "R83") (pin "2") (pinfunction "2_2") (pintype "passive"))
    )
    (net (code "155") (name "Net-(Q33-D)") (class "Default")
      (node (ref "K11") (pin "A1") (pinfunction "A1_A1") (pintype "passive"))
      (node (ref "Q33") (pin "3") (pinfunction "D_3") (pintype "passive"))
    )
    (net (code "156") (name "Net-(Q33-G)") (class "Default")
      (node (ref "C26") (pin "2") (pinfunction "2_2") (pintype "passive"))
      (node (ref "Q33") (pin "1") (pinfunction "G_1") (pintype "passive"))
      (node (ref "R93") (pin "1") (pinfunction "1_1") (pintype "passive"))
      (node (ref "R95") (pin "2") (pinfunction "2_2") (pintype "passive"))
    )
    (net (code "157") (name "Net-(Q34-D)") (class "Default")
      (node (ref "K12") (pin "A1") (pinfunction "A1_A1") (pintype "passive"))
      (node (ref "Q34") (pin "3") (pinfunction "D_3") (pintype "passive"))
    )
    (net (code "158") (name "Net-(Q34-G)") (class "Default")
      (node (ref "C27") (pin "2") (pinfunction "2_2") (pintype "passive"))
      (node (ref "Q34") (pin "1") (pinfunction "G_1") (pintype "passive"))
      (node (ref "R94") (pin "1") (pinfunction "1_1") (pintype "passive"))
      (node (ref "R97") (pin "2") (pinfunction "2_2") (pintype "passive"))
    )
    (net (code "159") (name "Net-(Q35-D)") (class "Default")
      (node (ref "K11") (pin "A2") (pinfunction "A2_A2") (pintype "passive"))
      (node (ref "Q35") (pin "3") (pinfunction "D_3") (pintype "passive"))
    )
    (net (code "160") (name "Net-(Q35-G)") (class "Default")
      (node (ref "C28") (pin "2") (pinfunction "2_2") (pintype "passive"))
      (node (ref "Q35") (pin "1") (pinfunction "G_1") (pintype "passive"))
      (node (ref "R91") (pin "1") (pinfunction "1_1") (pintype "passive"))
      (node (ref "R96") (pin "2") (pinfunction "2_2") (pintype "passive"))
    )
    (net (code "161") (name "Net-(Q36-D)") (class "Default")
      (node (ref "K12") (pin "A2") (pinfunction "A2_A2") (pintype "passive"))
      (node (ref "Q36") (pin "3") (pinfunction "D_3") (pintype "passive"))
    )
    (net (code "162") (name "Net-(Q36-G)") (class "Default")
      (node (ref "C29") (pin "2") (pinfunction "2_2") (pintype "passive"))
      (node (ref "Q36") (pin "1") (pinfunction "G_1") (pintype "passive"))
      (node (ref "R92") (pin "1") (pinfunction "1_1") (pintype "passive"))
      (node (ref "R98") (pin "2") (pinfunction "2_2") (pintype "passive"))
    )
    (net (code "163") (name "Net-(Q37-D)") (class "Default")
      (node (ref "K13") (pin "A1") (pinfunction "A1_A1") (pintype "passive"))
      (node (ref "Q37") (pin "3") (pinfunction "D_3") (pintype "passive"))
    )
    (net (code "164") (name "Net-(Q37-G)") (class "Default")
      (node (ref "C30") (pin "2") (pinfunction "2_2") (pintype "passive"))
      (node (ref "Q37") (pin "1") (pinfunction "G_1") (pintype "passive"))
      (node (ref "R100") (pin "1") (pinfunction "1_1") (pintype "passive"))
      (node (ref "R101") (pin "2") (pinfunction "2_2") (pintype "passive"))
    )
    (net (code "165") (name "Net-(Q38-D)") (class "Default")
      (node (ref "K13") (pin "A2") (pinfunction "A2_A2") (pintype "passive"))
      (node (ref "Q38") (pin "3") (pinfunction "D_3") (pintype "passive"))
    )
    (net (code "166") (name "Net-(Q38-G)") (class "Default")
      (node (ref "C31") (pin "2") (pinfunction "2_2") (pintype "passive"))
      (node (ref "Q38") (pin "1") (pinfunction "G_1") (pintype "passive"))
      (node (ref "R102") (pin "2") (pinfunction "2_2") (pintype "passive"))
      (node (ref "R99") (pin "1") (pinfunction "1_1") (pintype "passive"))
    )
    (net (code "167") (name "Net-(Q39-D)") (class "Default")
      (node (ref "K14") (pin "A1") (pinfunction "A1_A1") (pintype "passive"))
      (node (ref "Q39") (pin "3") (pinfunction "D_3") (pintype "passive"))
    )
    (net (code "168") (name "Net-(Q39-G)") (class "Default")
      (node (ref "C32") (pin "2") (pinfunction "2_2") (pintype "passive"))
      (node (ref "Q39") (pin "1") (pinfunction "G_1") (pintype "passive"))
      (node (ref "R104") (pin "1") (pinfunction "1_1") (pintype "passive"))
      (node (ref "R105") (pin "2") (pinfunction "2_2") (pintype "passive"))
    )
    (net (code "169") (name "Net-(Q40-D)") (class "Default")
      (node (ref "K14") (pin "A2") (pinfunction "A2_A2") (pintype "passive"))
      (node (ref "Q40") (pin "3") (pinfunction "D_3") (pintype "passive"))
    )
    (net (code "170") (name "Net-(Q40-G)") (class "Default")
      (node (ref "C37") (pin "2") (pinfunction "2_2") (pintype "passive"))
      (node (ref "Q40") (pin "1") (pinfunction "G_1") (pintype "passive"))
      (node (ref "R103") (pin "1") (pinfunction "1_1") (pintype "passive"))
      (node (ref "R106") (pin "2") (pinfunction "2_2") (pintype "passive"))
    )
    (net (code "171") (name "Net-(Q41-D)") (class "Default")
      (node (ref "K15") (pin "A1") (pinfunction "A1_A1") (pintype "passive"))
      (node (ref "Q41") (pin "3") (pinfunction "D_3") (pintype "passive"))
    )
    (net (code "172") (name "Net-(Q41-G)") (class "Default")
      (node (ref "C38") (pin "2") (pinfunction "2_2") (pintype "passive"))
      (node (ref "Q41") (pin "1") (pinfunction "G_1") (pintype "passive"))
      (node (ref "R108") (pin "1") (pinfunction "1_1") (pintype "passive"))
      (node (ref "R109") (pin "2") (pinfunction "2_2") (pintype "passive"))
    )
    (net (code "173") (name "Net-(Q42-D)") (class "Default")
      (node (ref "K15") (pin "A2") (pinfunction "A2_A2") (pintype "passive"))
      (node (ref "Q42") (pin "3") (pinfunction "D_3") (pintype "passive"))
    )
    (net (code "174") (name "Net-(Q42-G)") (class "Default")
      (node (ref "C39") (pin "2") (pinfunction "2_2") (pintype "passive"))
      (node (ref "Q42") (pin "1") (pinfunction "G_1") (pintype "passive"))
      (node (ref "R107") (pin "1") (pinfunction "1_1") (pintype "passive"))
      (node (ref "R110") (pin "2") (pinfunction "2_2") (pintype "passive"))
    )
    (net (code "175") (name "Net-(Q43-D)") (class "Default")
      (node (ref "K16") (pin "A1") (pinfunction "A1_A1") (pintype "passive"))
      (node (ref "Q43") (pin "3") (pinfunction "D_3") (pintype "passive"))
    )
    (net (code "176") (name "Net-(Q43-G)") (class "Default")
      (node (ref "C40") (pin "2") (pinfunction "2_2") (pintype "passive"))
      (node (ref "Q43") (pin "1") (pinfunction "G_1") (pintype "passive"))
      (node (ref "R112") (pin "1") (pinfunction "1_1") (pintype "passive"))
      (node (ref "R113") (pin "2") (pinfunction "2_2") (pintype "passive"))
    )
    (net (code "177") (name "Net-(Q44-D)") (class "Default")
      (node (ref "K16") (pin "A2") (pinfunction "A2_A2") (pintype "passive"))
      (node (ref "Q44") (pin "3") (pinfunction "D_3") (pintype "passive"))
    )
    (net (code "178") (name "Net-(Q44-G)") (class "Default")
      (node (ref "C41") (pin "2") (pinfunction "2_2") (pintype "passive"))
      (node (ref "Q44") (pin "1") (pinfunction "G_1") (pintype "passive"))
      (node (ref "R111") (pin "1") (pinfunction "1_1") (pintype "passive"))
      (node (ref "R114") (pin "2") (pinfunction "2_2") (pintype "passive"))
    )
    (net (code "179") (name "Net-(Q45-D)") (class "Default")
      (node (ref "K17") (pin "A1") (pinfunction "A1_A1") (pintype "passive"))
      (node (ref "Q45") (pin "3") (pinfunction "D_3") (pintype "passive"))
    )
    (net (code "180") (name "Net-(Q45-G)") (class "Default")
      (node (ref "C42") (pin "2") (pinfunction "2_2") (pintype "passive"))
      (node (ref "Q45") (pin "1") (pinfunction "G_1") (pintype "passive"))
      (node (ref "R116") (pin "1") (pinfunction "1_1") (pintype "passive"))
      (node (ref "R117") (pin "2") (pinfunction "2_2") (pintype "passive"))
    )
    (net (code "181") (name "Net-(Q46-D)") (class "Default")
      (node (ref "K17") (pin "A2") (pinfunction "A2_A2") (pintype "passive"))
      (node (ref "Q46") (pin "3") (pinfunction "D_3") (pintype "passive"))
    )
    (net (code "182") (name "Net-(Q46-G)") (class "Default")
      (node (ref "C43") (pin "2") (pinfunction "2_2") (pintype "passive"))
      (node (ref "Q46") (pin "1") (pinfunction "G_1") (pintype "passive"))
      (node (ref "R115") (pin "1") (pinfunction "1_1") (pintype "passive"))
      (node (ref "R118") (pin "2") (pinfunction "2_2") (pintype "passive"))
    )
    (net (code "183") (name "Net-(Q47-D)") (class "Default")
      (node (ref "K18") (pin "A1") (pinfunction "A1_A1") (pintype "passive"))
      (node (ref "Q47") (pin "3") (pinfunction "D_3") (pintype "passive"))
    )
    (net (code "184") (name "Net-(Q47-G)") (class "Default")
      (node (ref "C44") (pin "2") (pinfunction "2_2") (pintype "passive"))
      (node (ref "Q47") (pin "1") (pinfunction "G_1") (pintype "passive"))
      (node (ref "R120") (pin "1") (pinfunction "1_1") (pintype "passive"))
      (node (ref "R121") (pin "2") (pinfunction "2_2") (pintype "passive"))
    )
    (net (code "185") (name "Net-(Q48-D)") (class "Default")
      (node (ref "K18") (pin "A2") (pinfunction "A2_A2") (pintype "passive"))
      (node (ref "Q48") (pin "3") (pinfunction "D_3") (pintype "passive"))
    )
    (net (code "186") (name "Net-(Q48-G)") (class "Default")
      (node (ref "C45") (pin "2") (pinfunction "2_2") (pintype "passive"))
      (node (ref "Q48") (pin "1") (pinfunction "G_1") (pintype "passive"))
      (node (ref "R119") (pin "1") (pinfunction "1_1") (pintype "passive"))
      (node (ref "R122") (pin "2") (pinfunction "2_2") (pintype "passive"))
    )
    (net (code "187") (name "Net-(Q49-D)") (class "Default")
      (node (ref "K19") (pin "A1") (pinfunction "A1_A1") (pintype "passive"))
      (node (ref "Q49") (pin "3") (pinfunction "D_3") (pintype "passive"))
    )
    (net (code "188") (name "Net-(Q49-G)") (class "Default")
      (node (ref "C46") (pin "2") (pinfunction "2_2") (pintype "passive"))
      (node (ref "Q49") (pin "1") (pinfunction "G_1") (pintype "passive"))
      (node (ref "R124") (pin "1") (pinfunction "1_1") (pintype "passive"))
      (node (ref "R125") (pin "2") (pinfunction "2_2") (pintype "passive"))
    )
    (net (code "189") (name "Net-(Q50-D)") (class "Default")
      (node (ref "K19") (pin "A2") (pinfunction "A2_A2") (pintype "passive"))
      (node (ref "Q50") (pin "3") (pinfunction "D_3") (pintype "passive"))
    )
    (net (code "190") (name "Net-(Q50-G)") (class "Default")
      (node (ref "C47") (pin "2") (pinfunction "2_2") (pintype "passive"))
      (node (ref "Q50") (pin "1") (pinfunction "G_1") (pintype "passive"))
      (node (ref "R123") (pin "1") (pinfunction "1_1") (pintype "passive"))
      (node (ref "R126") (pin "2") (pinfunction "2_2") (pintype "passive"))
    )
    (net (code "191") (name "Net-(Q51-D)") (class "Default")
      (node (ref "K20") (pin "A1") (pinfunction "A1_A1") (pintype "passive"))
      (node (ref "Q51") (pin "3") (pinfunction "D_3") (pintype "passive"))
    )
    (net (code "192") (name "Net-(Q51-G)") (class "Default")
      (node (ref "C48") (pin "2") (pinfunction "2_2") (pintype "passive"))
      (node (ref "Q51") (pin "1") (pinfunction "G_1") (pintype "passive"))
      (node (ref "R128") (pin "1") (pinfunction "1_1") (pintype "passive"))
      (node (ref "R129") (pin "2") (pinfunction "2_2") (pintype "passive"))
    )
    (net (code "193") (name "Net-(Q52-D)") (class "Default")
      (node (ref "K20") (pin "A2") (pinfunction "A2_A2") (pintype "passive"))
      (node (ref "Q52") (pin "3") (pinfunction "D_3") (pintype "passive"))
    )
    (net (code "194") (name "Net-(Q52-G)") (class "Default")
      (node (ref "C49") (pin "2") (pinfunction "2_2") (pintype "passive"))
      (node (ref "Q52") (pin "1") (pinfunction "G_1") (pintype "passive"))
      (node (ref "R127") (pin "1") (pinfunction "1_1") (pintype "passive"))
      (node (ref "R130") (pin "2") (pinfunction "2_2") (pintype "passive"))
    )
    (net (code "195") (name "Net-(Q53-D)") (class "Default")
      (node (ref "K21") (pin "A1") (pinfunction "A1_A1") (pintype "passive"))
      (node (ref "Q53") (pin "3") (pinfunction "D_3") (pintype "passive"))
    )
    (net (code "196") (name "Net-(Q53-G)") (class "Default")
      (node (ref "C50") (pin "2") (pinfunction "2_2") (pintype "passive"))
      (node (ref "Q53") (pin "1") (pinfunction "G_1") (pintype "passive"))
      (node (ref "R132") (pin "1") (pinfunction "1_1") (pintype "passive"))
      (node (ref "R133") (pin "2") (pinfunction "2_2") (pintype "passive"))
    )
    (net (code "197") (name "Net-(Q54-D)") (class "Default")
      (node (ref "K21") (pin "A2") (pinfunction "A2_A2") (pintype "passive"))
      (node (ref "Q54") (pin "3") (pinfunction "D_3") (pintype "passive"))
    )
    (net (code "198") (name "Net-(Q54-G)") (class "Default")
      (node (ref "C51") (pin "2") (pinfunction "2_2") (pintype "passive"))
      (node (ref "Q54") (pin "1") (pinfunction "G_1") (pintype "passive"))
      (node (ref "R131") (pin "1") (pinfunction "1_1") (pintype "passive"))
      (node (ref "R134") (pin "2") (pinfunction "2_2") (pintype "passive"))
    )
    (net (code "199") (name "Net-(Q55-D)") (class "Default")
      (node (ref "K22") (pin "A1") (pinfunction "A1_A1") (pintype "passive"))
      (node (ref "Q55") (pin "3") (pinfunction "D_3") (pintype "passive"))
    )
    (net (code "200") (name "Net-(Q55-G)") (class "Default")
      (node (ref "C52") (pin "2") (pinfunction "2_2") (pintype "passive"))
      (node (ref "Q55") (pin "1") (pinfunction "G_1") (pintype "passive"))
      (node (ref "R136") (pin "1") (pinfunction "1_1") (pintype "passive"))
      (node (ref "R137") (pin "2") (pinfunction "2_2") (pintype "passive"))
    )
    (net (code "201") (name "Net-(Q56-D)") (class "Default")
      (node (ref "K22") (pin "A2") (pinfunction "A2_A2") (pintype "passive"))
      (node (ref "Q56") (pin "3") (pinfunction "D_3") (pintype "passive"))
    )
    (net (code "202") (name "Net-(Q56-G)") (class "Default")
      (node (ref "C53") (pin "2") (pinfunction "2_2") (pintype "passive"))
      (node (ref "Q56") (pin "1") (pinfunction "G_1") (pintype "passive"))
      (node (ref "R135") (pin "1") (pinfunction "1_1") (pintype "passive"))
      (node (ref "R138") (pin "2") (pinfunction "2_2") (pintype "passive"))
    )
    (net (code "203") (name "Net-(Q57-D)") (class "Default")
      (node (ref "K23") (pin "A1") (pinfunction "A1_A1") (pintype "passive"))
      (node (ref "Q57") (pin "3") (pinfunction "D_3") (pintype "passive"))
    )
    (net (code "204") (name "Net-(Q57-G)") (class "Default")
      (node (ref "C54") (pin "2") (pinfunction "2_2") (pintype "passive"))
      (node (ref "Q57") (pin "1") (pinfunction "G_1") (pintype "passive"))
      (node (ref "R140") (pin "1") (pinfunction "1_1") (pintype "passive"))
      (node (ref "R141") (pin "2") (pinfunction "2_2") (pintype "passive"))
    )
    (net (code "205") (name "Net-(Q58-D)") (class "Default")
      (node (ref "K23") (pin "A2") (pinfunction "A2_A2") (pintype "passive"))
      (node (ref "Q58") (pin "3") (pinfunction "D_3") (pintype "passive"))
    )
    (net (code "206") (name "Net-(Q58-G)") (class "Default")
      (node (ref "C55") (pin "2") (pinfunction "2_2") (pintype "passive"))
      (node (ref "Q58") (pin "1") (pinfunction "G_1") (pintype "passive"))
      (node (ref "R139") (pin "1") (pinfunction "1_1") (pintype "passive"))
      (node (ref "R142") (pin "2") (pinfunction "2_2") (pintype "passive"))
    )
    (net (code "207") (name "Net-(Q59-D)") (class "Default")
      (node (ref "K24") (pin "A1") (pinfunction "A1_A1") (pintype "passive"))
      (node (ref "Q59") (pin "3") (pinfunction "D_3") (pintype "passive"))
    )
    (net (code "208") (name "Net-(Q59-G)") (class "Default")
      (node (ref "C56") (pin "2") (pinfunction "2_2") (pintype "passive"))
      (node (ref "Q59") (pin "1") (pinfunction "G_1") (pintype "passive"))
      (node (ref "R144") (pin "1") (pinfunction "1_1") (pintype "passive"))
      (node (ref "R145") (pin "2") (pinfunction "2_2") (pintype "passive"))
    )
    (net (code "209") (name "Net-(Q60-D)") (class "Default")
      (node (ref "K24") (pin "A2") (pinfunction "A2_A2") (pintype "passive"))
      (node (ref "Q60") (pin "3") (pinfunction "D_3") (pintype "passive"))
    )
    (net (code "210") (name "Net-(Q60-G)") (class "Default")
      (node (ref "C57") (pin "2") (pinfunction "2_2") (pintype "passive"))
      (node (ref "Q60") (pin "1") (pinfunction "G_1") (pintype "passive"))
      (node (ref "R143") (pin "1") (pinfunction "1_1") (pintype "passive"))
      (node (ref "R146") (pin "2") (pinfunction "2_2") (pintype "passive"))
    )
    (net (code "211") (name "Net-(Q61-D)") (class "Default")
      (node (ref "K25") (pin "A1") (pinfunction "A1_A1") (pintype "passive"))
      (node (ref "Q61") (pin "3") (pinfunction "D_3") (pintype "passive"))
    )
    (net (code "212") (name "Net-(Q61-G)") (class "Default")
      (node (ref "C58") (pin "2") (pinfunction "2_2") (pintype "passive"))
      (node (ref "Q61") (pin "1") (pinfunction "G_1") (pintype "passive"))
      (node (ref "R148") (pin "1") (pinfunction "1_1") (pintype "passive"))
      (node (ref "R149") (pin "2") (pinfunction "2_2") (pintype "passive"))
    )
    (net (code "213") (name "Net-(Q62-D)") (class "Default")
      (node (ref "K25") (pin "A2") (pinfunction "A2_A2") (pintype "passive"))
      (node (ref "Q62") (pin "3") (pinfunction "D_3") (pintype "passive"))
    )
    (net (code "214") (name "Net-(Q62-G)") (class "Default")
      (node (ref "C59") (pin "2") (pinfunction "2_2") (pintype "passive"))
      (node (ref "Q62") (pin "1") (pinfunction "G_1") (pintype "passive"))
      (node (ref "R147") (pin "1") (pinfunction "1_1") (pintype "passive"))
      (node (ref "R150") (pin "2") (pinfunction "2_2") (pintype "passive"))
    )
    (net (code "215") (name "Net-(Q63-D)") (class "Default")
      (node (ref "K26") (pin "A1") (pinfunction "A1_A1") (pintype "passive"))
      (node (ref "Q63") (pin "3") (pinfunction "D_3") (pintype "passive"))
    )
    (net (code "216") (name "Net-(Q63-G)") (class "Default")
      (node (ref "C60") (pin "2") (pinfunction "2_2") (pintype "passive"))
      (node (ref "Q63") (pin "1") (pinfunction "G_1") (pintype "passive"))
      (node (ref "R152") (pin "1") (pinfunction "1_1") (pintype "passive"))
      (node (ref "R153") (pin "2") (pinfunction "2_2") (pintype "passive"))
    )
    (net (code "217") (name "Net-(Q64-D)") (class "Default")
      (node (ref "K26") (pin "A2") (pinfunction "A2_A2") (pintype "passive"))
      (node (ref "Q64") (pin "3") (pinfunction "D_3") (pintype "passive"))
    )
    (net (code "218") (name "Net-(Q64-G)") (class "Default")
      (node (ref "C61") (pin "2") (pinfunction "2_2") (pintype "passive"))
      (node (ref "Q64") (pin "1") (pinfunction "G_1") (pintype "passive"))
      (node (ref "R151") (pin "1") (pinfunction "1_1") (pintype "passive"))
      (node (ref "R154") (pin "2") (pinfunction "2_2") (pintype "passive"))
    )
  )
)
